# JKW_standalone.net
KiCad netlist of a schematic drawn in EAGLE
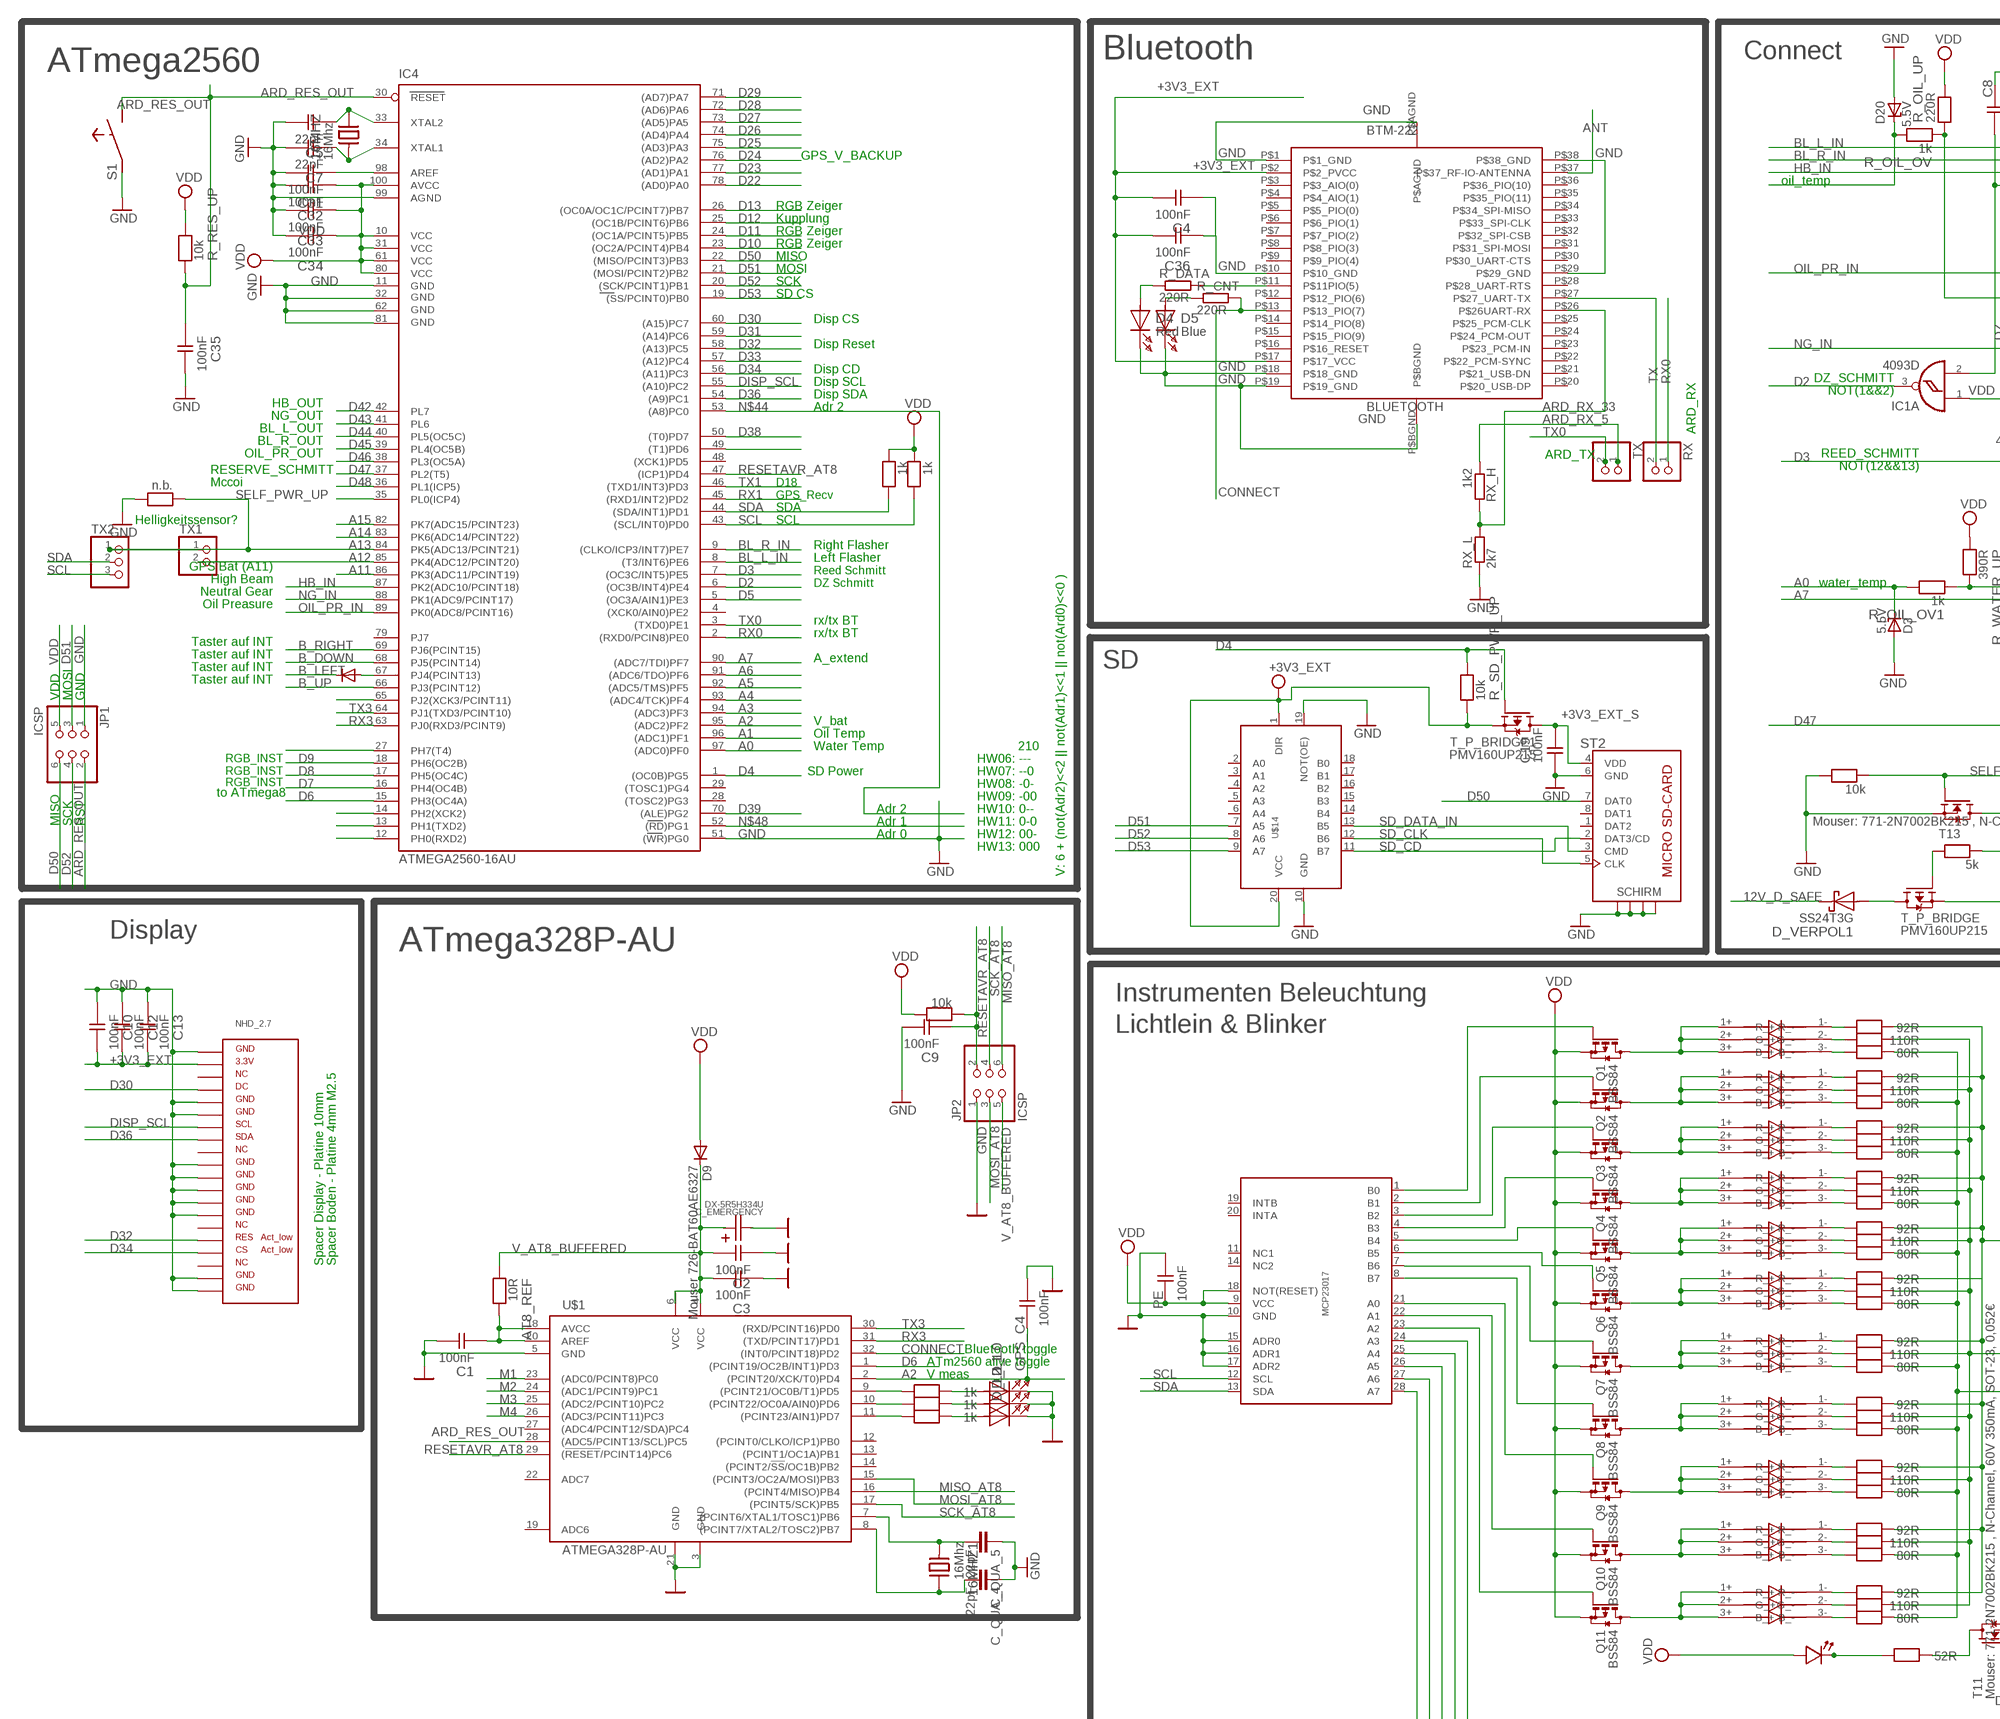
[diagram p0: schematic, sheet 1, part 1 of 3]
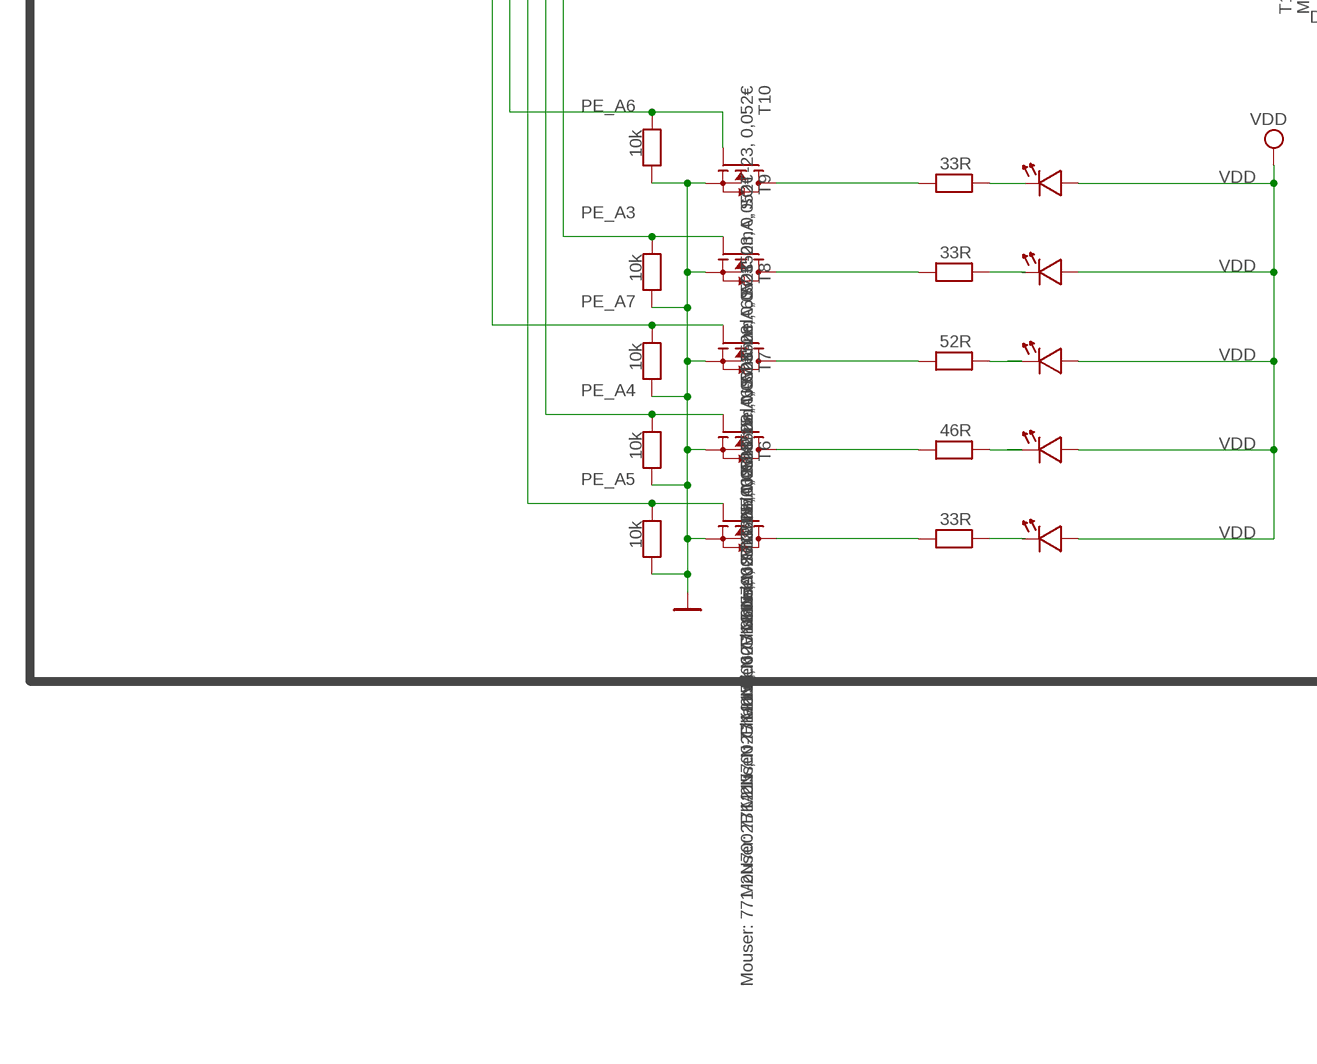
[diagram p1: schematic, sheet 1, part 2 of 3]
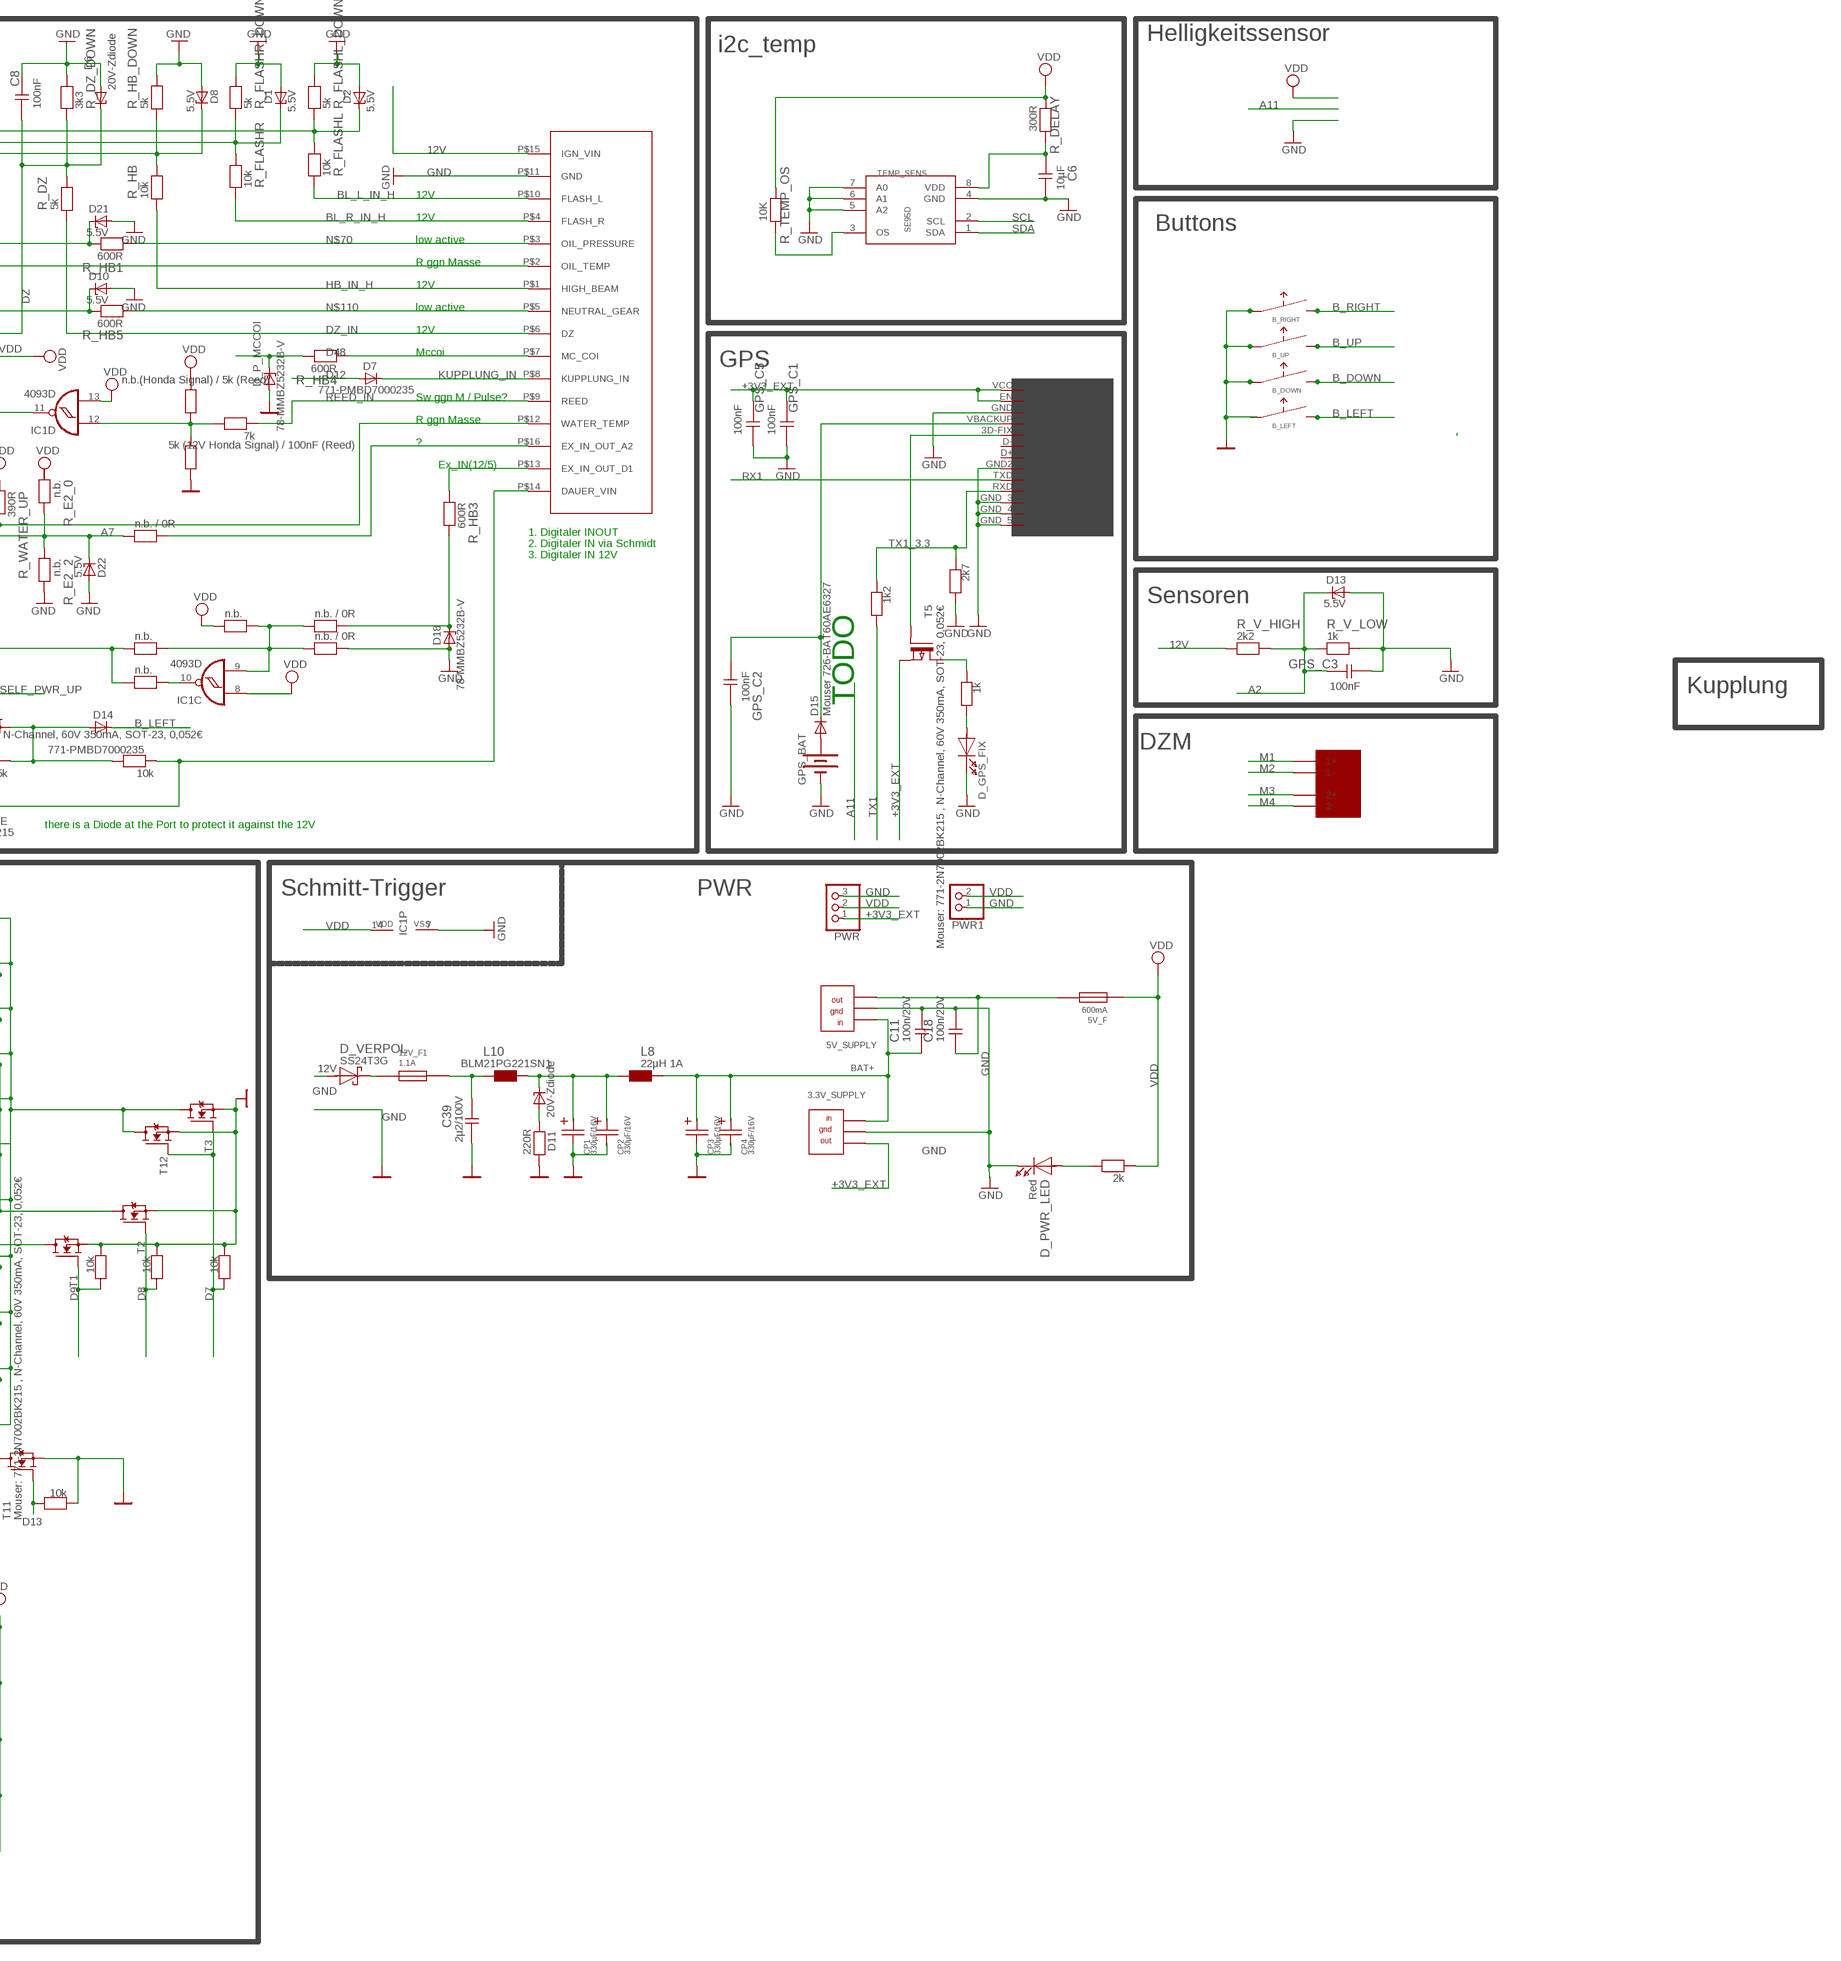
[diagram p2: schematic, sheet 1, part 3 of 3]

(export (version "E")
  (design (tool "Eeschema 10.0.6"))
  (components
    (comp (ref "3.3V_SUPPLY")
      (value "OKI78SR3.31.5WHC")
      (footprint "eagle-import:OKI-78SR")
      (libsource (lib "eagle-import") (part "OKI-78SR"))
    )
    (comp (ref "5V_F")
      (value "600mA")
      (footprint "eagle-import:POLY_FUSE")
      (libsource (lib "eagle-import") (part "POLY_FUSE"))
    )
    (comp (ref "5V_SUPPLY")
      (value "OKI78SR51.5W36HC")
      (footprint "eagle-import:OKI-78SR")
      (libsource (lib "eagle-import") (part "OKI-78SR"))
    )
    (comp (ref "12V_F1")
      (value "1.1A")
      (footprint "eagle-import:POLY_FUSE")
      (libsource (lib "eagle-import") (part "POLY_FUSE"))
    )
    (comp (ref "16MHZ")
      (value "16Mhz")
      (footprint "eagle-import:XT-HC49S-SMD")
      (libsource (lib "eagle-import") (part "XT-HC49-SMD"))
    )
    (comp (ref "16MHZ1")
      (value "16Mhz")
      (footprint "eagle-import:XT-HC49S-SMD")
      (libsource (lib "eagle-import") (part "XT-HC49-SMD"))
    )
    (comp (ref "AT8_REF")
      (value "10R")
      (footprint "eagle-import:0805")
      (libsource (lib "eagle-import") (part "R0805"))
    )
    (comp (ref "BLUETOOTH")
      (value "BTM-222")
      (footprint "eagle-import:BTM-222")
      (libsource (lib "eagle-import") (part "BTM-222"))
    )
    (comp (ref "B_DOWN")
      (value "SMD_TASTER_MIT_KAPPE")
      (footprint "eagle-import:SMD_DRUCKTASTER")
      (libsource (lib "eagle-import") (part "SMD_TASTER_MIT_KAPPE"))
    )
    (comp (ref "B_LEFT")
      (value "SMD_TASTER_MIT_KAPPE")
      (footprint "eagle-import:SMD_DRUCKTASTER")
      (libsource (lib "eagle-import") (part "SMD_TASTER_MIT_KAPPE"))
    )
    (comp (ref "B_RIGHT")
      (value "SMD_TASTER_MIT_KAPPE")
      (footprint "eagle-import:SMD_DRUCKTASTER")
      (libsource (lib "eagle-import") (part "SMD_TASTER_MIT_KAPPE"))
    )
    (comp (ref "B_UP")
      (value "SMD_TASTER_MIT_KAPPE")
      (footprint "eagle-import:SMD_DRUCKTASTER")
      (libsource (lib "eagle-import") (part "SMD_TASTER_MIT_KAPPE"))
    )
    (comp (ref "C1")
      (value "100nF")
      (footprint "eagle-import:0805")
      (libsource (lib "eagle-import") (part "C0805"))
    )
    (comp (ref "C2")
      (value "100nF")
      (footprint "eagle-import:0805")
      (libsource (lib "eagle-import") (part "C0805"))
    )
    (comp (ref "C3")
      (value "100nF")
      (footprint "eagle-import:0805")
      (libsource (lib "eagle-import") (part "C0805"))
    )
    (comp (ref "C4")
      (value "100nF")
      (footprint "eagle-import:0805")
      (libsource (lib "eagle-import") (part "C0805"))
    )
    (comp (ref "C5")
      (value "22pF")
      (footprint "eagle-import:0805")
      (libsource (lib "eagle-import") (part "C0805"))
    )
    (comp (ref "C6")
      (value "10µF")
      (footprint "eagle-import:0805")
      (libsource (lib "eagle-import") (part "C0805"))
    )
    (comp (ref "C7")
      (value "22pF")
      (footprint "eagle-import:0805")
      (libsource (lib "eagle-import") (part "C0805"))
    )
    (comp (ref "C8")
      (value "100nF")
      (footprint "eagle-import:0805")
      (libsource (lib "eagle-import") (part "C0805"))
    )
    (comp (ref "C9")
      (value "100nF")
      (footprint "eagle-import:0805")
      (libsource (lib "eagle-import") (part "C0805"))
    )
    (comp (ref "C10")
      (value "100nF")
      (footprint "eagle-import:0805")
      (libsource (lib "eagle-import") (part "C0805"))
    )
    (comp (ref "C11")
      (value "100n/20V")
      (footprint "eagle-import:0805")
      (libsource (lib "eagle-import") (part "C0805"))
    )
    (comp (ref "C12")
      (value "100nF")
      (footprint "eagle-import:0805")
      (libsource (lib "eagle-import") (part "C0805"))
    )
    (comp (ref "C13")
      (value "100nF")
      (footprint "eagle-import:0805")
      (libsource (lib "eagle-import") (part "C0805"))
    )
    (comp (ref "C18")
      (value "100n/20V")
      (footprint "eagle-import:0805")
      (libsource (lib "eagle-import") (part "C0805"))
    )
    (comp (ref "C19")
      (value "100nF")
      (footprint "eagle-import:0805")
      (libsource (lib "eagle-import") (part "C0805"))
    )
    (comp (ref "C31")
      (value "100nF")
      (footprint "eagle-import:0805")
      (libsource (lib "eagle-import") (part "C0805"))
    )
    (comp (ref "C32")
      (value "100nF")
      (footprint "eagle-import:0805")
      (libsource (lib "eagle-import") (part "C0805"))
    )
    (comp (ref "C33")
      (value "100nF")
      (footprint "eagle-import:0805")
      (libsource (lib "eagle-import") (part "C0805"))
    )
    (comp (ref "C34")
      (value "100nF")
      (footprint "eagle-import:0805")
      (libsource (lib "eagle-import") (part "C0805"))
    )
    (comp (ref "C35")
      (value "100nF")
      (footprint "eagle-import:0805")
      (libsource (lib "eagle-import") (part "C0805"))
    )
    (comp (ref "C36")
      (value "100nF")
      (footprint "eagle-import:0805")
      (libsource (lib "eagle-import") (part "C0805"))
    )
    (comp (ref "C39")
      (value "2µ2/100V")
      (footprint "eagle-import:0805")
      (libsource (lib "eagle-import") (part "C0805"))
    )
    (comp (ref "CP1")
      (value "330µF/16V")
      (footprint "eagle-import:SMD_SMT_6.6_6.6")
      (libsource (lib "eagle-import") (part "C_SMD_SMP"))
    )
    (comp (ref "CP2")
      (value "330µF/16V")
      (footprint "eagle-import:SMD_SMT_6.6_6.6")
      (libsource (lib "eagle-import") (part "C_SMD_SMP"))
    )
    (comp (ref "CP3")
      (value "330µF/16V")
      (footprint "eagle-import:SMD_SMT_6.6_6.6")
      (libsource (lib "eagle-import") (part "C_SMD_SMP"))
    )
    (comp (ref "CP4")
      (value "330µF/16V")
      (footprint "eagle-import:SMD_SMT_6.6_6.6")
      (libsource (lib "eagle-import") (part "C_SMD_SMP"))
    )
    (comp (ref "C_EMERGENCY")
      (value "DX-5R5H334U")
      (footprint "eagle-import:GOLDCAP")
      (libsource (lib "eagle-import") (part "DX-5R5H334U"))
    )
    (comp (ref "C_QUA_4")
      (value "22pF")
      (footprint "eagle-import:C0805")
      (libsource (lib "eagle-import") (part "C-EUC0805"))
    )
    (comp (ref "C_QUA_5")
      (value "22pF")
      (footprint "eagle-import:C0805")
      (libsource (lib "eagle-import") (part "C-EUC0805"))
    )
    (comp (ref "D1")
      (value "5.5V")
      (footprint "eagle-import:SOT23")
      (libsource (lib "eagle-import") (part "ZENER-DIODESOT23"))
    )
    (comp (ref "D2")
      (value "5.5V")
      (footprint "eagle-import:SOT23")
      (libsource (lib "eagle-import") (part "ZENER-DIODESOT23"))
    )
    (comp (ref "D3")
      (value "5.5V")
      (footprint "eagle-import:SOT23")
      (libsource (lib "eagle-import") (part "ZENER-DIODESOT23"))
    )
    (comp (ref "D4")
      (value "Red")
      (footprint "eagle-import:LED-0805")
      (libsource (lib "eagle-import") (part "LED0805"))
    )
    (comp (ref "D5")
      (value "Blue")
      (footprint "eagle-import:LED-0805")
      (libsource (lib "eagle-import") (part "LED0805"))
    )
    (comp (ref "D6")
      (value "20V-Zdiode")
      (footprint "eagle-import:SOT23")
      (libsource (lib "eagle-import") (part "ZENER-DIODESOT23"))
    )
    (comp (ref "D7")
      (value "771-PMBD7000235")
      (footprint "eagle-import:SOT23")
      (libsource (lib "eagle-import") (part "D-A1-C3"))
    )
    (comp (ref "D8")
      (value "5.5V")
      (footprint "eagle-import:SOT23")
      (libsource (lib "eagle-import") (part "ZENER-DIODESOT23"))
    )
    (comp (ref "D9")
      (value "Mouser 726-BAT60AE6327")
      (footprint "eagle-import:SOD323-W")
      (libsource (lib "eagle-import") (part "DIODE-SOD323-W"))
    )
    (comp (ref "D10")
      (value "5.5V")
      (footprint "eagle-import:SOT23")
      (libsource (lib "eagle-import") (part "ZENER-DIODESOT23"))
    )
    (comp (ref "D11")
      (value "20V-Zdiode")
      (footprint "eagle-import:SOT23")
      (libsource (lib "eagle-import") (part "ZENER-DIODESOT23"))
    )
    (comp (ref "D12")
      (value "771-PMBD7000235")
      (footprint "eagle-import:SOT23")
      (libsource (lib "eagle-import") (part "D-A1-C3"))
    )
    (comp (ref "D13")
      (value "5.5V")
      (footprint "eagle-import:SOT23")
      (libsource (lib "eagle-import") (part "ZENER-DIODESOT23"))
    )
    (comp (ref "D14")
      (value "771-PMBD7000235")
      (footprint "eagle-import:SOT23")
      (libsource (lib "eagle-import") (part "D-A1-C3"))
    )
    (comp (ref "D15")
      (value "Mouser 726-BAT60AE6327")
      (footprint "eagle-import:SOD323-W")
      (libsource (lib "eagle-import") (part "DIODE-SOD323-W"))
    )
    (comp (ref "D18")
      (value "78-MMBZ5232B-V")
      (footprint "eagle-import:SOT23")
      (libsource (lib "eagle-import") (part "ZENER-DIODESOT23"))
    )
    (comp (ref "D20")
      (value "5.5V")
      (footprint "eagle-import:SOT23")
      (libsource (lib "eagle-import") (part "ZENER-DIODESOT23"))
    )
    (comp (ref "D21")
      (value "5.5V")
      (footprint "eagle-import:SOT23")
      (libsource (lib "eagle-import") (part "ZENER-DIODESOT23"))
    )
    (comp (ref "D22")
      (value "5.5V")
      (footprint "eagle-import:SOT23")
      (libsource (lib "eagle-import") (part "ZENER-DIODESOT23"))
    )
    (comp (ref "D_GPS_FIX")
      (value "Red")
      (footprint "eagle-import:LED-0805")
      (libsource (lib "eagle-import") (part "LED0805"))
    )
    (comp (ref "D_GR_BLR")
      (value "PLCC4_LED")
      (footprint "eagle-import:PLCC-4")
      (libsource (lib "eagle-import") (part "PLCC4_LED"))
    )
    (comp (ref "D_GR_N")
      (value "PLCC4_LED")
      (footprint "eagle-import:PLCC-4")
      (libsource (lib "eagle-import") (part "PLCC4_LED"))
    )
    (comp (ref "D_L0")
      (value "LED0805")
      (footprint "eagle-import:LED-0805")
      (libsource (lib "eagle-import") (part "LED0805"))
    )
    (comp (ref "D_L1")
      (value "LED0805")
      (footprint "eagle-import:LED-0805")
      (libsource (lib "eagle-import") (part "LED0805"))
    )
    (comp (ref "D_L2")
      (value "LED0805")
      (footprint "eagle-import:LED-0805")
      (libsource (lib "eagle-import") (part "LED0805"))
    )
    (comp (ref "D_PWR_LED")
      (value "Red")
      (footprint "eagle-import:LED-0805")
      (libsource (lib "eagle-import") (part "LED0805"))
    )
    (comp (ref "D_P_MCCOI")
      (value "78-MMBZ5232B-V")
      (footprint "eagle-import:SOT23")
      (libsource (lib "eagle-import") (part "ZENER-DIODESOT23"))
    )
    (comp (ref "D_VERPOL")
      (value "SS24T3G")
      (footprint "eagle-import:SMB")
      (libsource (lib "eagle-import") (part "D-SSMB-A+K"))
    )
    (comp (ref "D_VERPOL1")
      (value "SS24T3G")
      (footprint "eagle-import:SMB")
      (libsource (lib "eagle-import") (part "D-SSMB-A+K"))
    )
    (comp (ref "GPS")
      (value "MT3329")
      (footprint "eagle-import:MT3329")
      (libsource (lib "eagle-import") (part "MT3329"))
    )
    (comp (ref "GPS_BAT")
      (value "F_908642")
      (footprint "eagle-import:BATTCON_12MM")
      (libsource (lib "eagle-import") (part "BATTERY12MM"))
    )
    (comp (ref "GPS_C1")
      (value "100nF")
      (footprint "eagle-import:0805")
      (libsource (lib "eagle-import") (part "C0805"))
    )
    (comp (ref "GPS_C2")
      (value "100nF")
      (footprint "eagle-import:0805")
      (libsource (lib "eagle-import") (part "C0805"))
    )
    (comp (ref "GPS_C3")
      (value "100nF")
      (footprint "eagle-import:0805")
      (libsource (lib "eagle-import") (part "C0805"))
    )
    (comp (ref "GPS_C4")
      (value "100nF")
      (footprint "eagle-import:0805")
      (libsource (lib "eagle-import") (part "C0805"))
    )
    (comp (ref "GPS_C5")
      (value "100nF")
      (footprint "eagle-import:0805")
      (libsource (lib "eagle-import") (part "C0805"))
    )
    (comp (ref "IC1")
      (value "4093D")
      (footprint "eagle-import:SO14")
      (libsource (lib "eagle-import") (part "4093D"))
    )
    (comp (ref "IC4")
      (value "ATMEGA2560-16AU")
      (footprint "eagle-import:TQFP100")
      (libsource (lib "eagle-import") (part "ATMEGAAU2560-16"))
    )
    (comp (ref "JP1")
      (value "ICSP")
      (footprint "eagle-import:2X03")
      (libsource (lib "eagle-import") (part "PINHD-2X3"))
    )
    (comp (ref "JP2")
      (value "ICSP")
      (footprint "eagle-import:2X03")
      (libsource (lib "eagle-import") (part "PINHD-2X3"))
    )
    (comp (ref "L8")
      (value "22µH 1A")
      (footprint "eagle-import:L-PD54")
      (libsource (lib "eagle-import") (part "LPD54"))
    )
    (comp (ref "L10")
      (value "BLM21PG221SN1")
      (footprint "eagle-import:0805+603")
      (libsource (lib "eagle-import") (part "L0808+0603"))
    )
    (comp (ref "NHD_2.7")
      (value "NHD_2.7_SOLO_RO")
      (footprint "eagle-import:NHD_2.7_SOLO_RO")
      (libsource (lib "eagle-import") (part "NHD_2.7_SOLO_RO"))
    )
    (comp (ref "PE")
      (value "100nF")
      (footprint "eagle-import:0805")
      (libsource (lib "eagle-import") (part "C0805"))
    )
    (comp (ref "PWR")
      (value "PINHD-1X3")
      (footprint "eagle-import:1X03")
      (libsource (lib "eagle-import") (part "PINHD-1X3"))
    )
    (comp (ref "PWR1")
      (value "PINHD-1X2")
      (footprint "eagle-import:1X02")
      (libsource (lib "eagle-import") (part "PINHD-1X2"))
    )
    (comp (ref "Q1")
      (value "BSS84")
      (footprint "eagle-import:SOT23")
      (libsource (lib "eagle-import") (part "BSS84"))
    )
    (comp (ref "Q2")
      (value "BSS84")
      (footprint "eagle-import:SOT23")
      (libsource (lib "eagle-import") (part "BSS84"))
    )
    (comp (ref "Q3")
      (value "BSS84")
      (footprint "eagle-import:SOT23")
      (libsource (lib "eagle-import") (part "BSS84"))
    )
    (comp (ref "Q4")
      (value "BSS84")
      (footprint "eagle-import:SOT23")
      (libsource (lib "eagle-import") (part "BSS84"))
    )
    (comp (ref "Q5")
      (value "BSS84")
      (footprint "eagle-import:SOT23")
      (libsource (lib "eagle-import") (part "BSS84"))
    )
    (comp (ref "Q6")
      (value "BSS84")
      (footprint "eagle-import:SOT23")
      (libsource (lib "eagle-import") (part "BSS84"))
    )
    (comp (ref "Q7")
      (value "BSS84")
      (footprint "eagle-import:SOT23")
      (libsource (lib "eagle-import") (part "BSS84"))
    )
    (comp (ref "Q8")
      (value "BSS84")
      (footprint "eagle-import:SOT23")
      (libsource (lib "eagle-import") (part "BSS84"))
    )
    (comp (ref "Q9")
      (value "BSS84")
      (footprint "eagle-import:SOT23")
      (libsource (lib "eagle-import") (part "BSS84"))
    )
    (comp (ref "Q10")
      (value "BSS84")
      (footprint "eagle-import:SOT23")
      (libsource (lib "eagle-import") (part "BSS84"))
    )
    (comp (ref "Q11")
      (value "BSS84")
      (footprint "eagle-import:SOT23")
      (libsource (lib "eagle-import") (part "BSS84"))
    )
    (comp (ref "RGB_1")
      (value "RGB_LED")
      (footprint "eagle-import:PLCC-6")
      (libsource (lib "eagle-import") (part "RGB_LED"))
    )
    (comp (ref "RGB_2")
      (value "RGB_LED")
      (footprint "eagle-import:PLCC-6")
      (libsource (lib "eagle-import") (part "RGB_LED"))
    )
    (comp (ref "RGB_3")
      (value "RGB_LED")
      (footprint "eagle-import:PLCC-6")
      (libsource (lib "eagle-import") (part "RGB_LED"))
    )
    (comp (ref "RGB_4")
      (value "RGB_LED")
      (footprint "eagle-import:PLCC-6")
      (libsource (lib "eagle-import") (part "RGB_LED"))
    )
    (comp (ref "RGB_5")
      (value "RGB_LED")
      (footprint "eagle-import:PLCC-6")
      (libsource (lib "eagle-import") (part "RGB_LED"))
    )
    (comp (ref "RGB_6")
      (value "RGB_LED")
      (footprint "eagle-import:PLCC-6")
      (libsource (lib "eagle-import") (part "RGB_LED"))
    )
    (comp (ref "RGB_7")
      (value "RGB_LED")
      (footprint "eagle-import:PLCC-6")
      (libsource (lib "eagle-import") (part "RGB_LED"))
    )
    (comp (ref "RGB_8")
      (value "RGB_LED")
      (footprint "eagle-import:PLCC-6")
      (libsource (lib "eagle-import") (part "RGB_LED"))
    )
    (comp (ref "RGB_9")
      (value "RGB_LED")
      (footprint "eagle-import:PLCC-6")
      (libsource (lib "eagle-import") (part "RGB_LED"))
    )
    (comp (ref "RGB_10")
      (value "RGB_LED")
      (footprint "eagle-import:PLCC-6")
      (libsource (lib "eagle-import") (part "RGB_LED"))
    )
    (comp (ref "RGB_11")
      (value "RGB_LED")
      (footprint "eagle-import:PLCC-6")
      (libsource (lib "eagle-import") (part "RGB_LED"))
    )
    (comp (ref "RX")
      (value "PINHD-1X2")
      (footprint "eagle-import:1X02")
      (libsource (lib "eagle-import") (part "PINHD-1X2"))
    )
    (comp (ref "RX_H")
      (value "1k2")
      (footprint "eagle-import:M0805")
      (libsource (lib "eagle-import") (part "resistor_R-EU_M0805"))
    )
    (comp (ref "RX_L")
      (value "2k7")
      (footprint "eagle-import:M0805")
      (libsource (lib "eagle-import") (part "resistor_R-EU_M0805"))
    )
    (comp (ref "R_BL_L")
      (value "33R")
      (footprint "eagle-import:0805")
      (libsource (lib "eagle-import") (part "R0805"))
    )
    (comp (ref "R_BL_L1")
      (value "n.b.")
      (footprint "eagle-import:0805")
      (libsource (lib "eagle-import") (part "R0805"))
    )
    (comp (ref "R_BL_R")
      (value "33R")
      (footprint "eagle-import:0805")
      (libsource (lib "eagle-import") (part "R0805"))
    )
    (comp (ref "R_B_LED_1")
      (value "80R")
      (footprint "eagle-import:0805")
      (libsource (lib "eagle-import") (part "R0805"))
    )
    (comp (ref "R_B_LED_2")
      (value "80R")
      (footprint "eagle-import:0805")
      (libsource (lib "eagle-import") (part "R0805"))
    )
    (comp (ref "R_B_LED_3")
      (value "80R")
      (footprint "eagle-import:0805")
      (libsource (lib "eagle-import") (part "R0805"))
    )
    (comp (ref "R_B_LED_4")
      (value "80R")
      (footprint "eagle-import:0805")
      (libsource (lib "eagle-import") (part "R0805"))
    )
    (comp (ref "R_B_LED_5")
      (value "80R")
      (footprint "eagle-import:0805")
      (libsource (lib "eagle-import") (part "R0805"))
    )
    (comp (ref "R_B_LED_6")
      (value "80R")
      (footprint "eagle-import:0805")
      (libsource (lib "eagle-import") (part "R0805"))
    )
    (comp (ref "R_B_LED_7")
      (value "80R")
      (footprint "eagle-import:0805")
      (libsource (lib "eagle-import") (part "R0805"))
    )
    (comp (ref "R_B_LED_8")
      (value "80R")
      (footprint "eagle-import:0805")
      (libsource (lib "eagle-import") (part "R0805"))
    )
    (comp (ref "R_B_LED_9")
      (value "80R")
      (footprint "eagle-import:0805")
      (libsource (lib "eagle-import") (part "R0805"))
    )
    (comp (ref "R_B_LED_10")
      (value "80R")
      (footprint "eagle-import:0805")
      (libsource (lib "eagle-import") (part "R0805"))
    )
    (comp (ref "R_B_LED_11")
      (value "80R")
      (footprint "eagle-import:0805")
      (libsource (lib "eagle-import") (part "R0805"))
    )
    (comp (ref "R_B_LED_12")
      (value "10k")
      (footprint "eagle-import:0805")
      (libsource (lib "eagle-import") (part "R0805"))
    )
    (comp (ref "R_B_LED_13")
      (value "10k")
      (footprint "eagle-import:0805")
      (libsource (lib "eagle-import") (part "R0805"))
    )
    (comp (ref "R_B_LED_14")
      (value "10k")
      (footprint "eagle-import:0805")
      (libsource (lib "eagle-import") (part "R0805"))
    )
    (comp (ref "R_B_LED_15")
      (value "10k")
      (footprint "eagle-import:0805")
      (libsource (lib "eagle-import") (part "R0805"))
    )
    (comp (ref "R_B_LED_16")
      (value "10k")
      (footprint "eagle-import:0805")
      (libsource (lib "eagle-import") (part "R0805"))
    )
    (comp (ref "R_B_LED_17")
      (value "10k")
      (footprint "eagle-import:0805")
      (libsource (lib "eagle-import") (part "R0805"))
    )
    (comp (ref "R_B_LED_18")
      (value "10k")
      (footprint "eagle-import:0805")
      (libsource (lib "eagle-import") (part "R0805"))
    )
    (comp (ref "R_B_LED_19")
      (value "10k")
      (footprint "eagle-import:0805")
      (libsource (lib "eagle-import") (part "R0805"))
    )
    (comp (ref "R_B_LED_20")
      (value "10k")
      (footprint "eagle-import:0805")
      (libsource (lib "eagle-import") (part "R0805"))
    )
    (comp (ref "R_CNT")
      (value "220R")
      (footprint "eagle-import:M0805")
      (libsource (lib "eagle-import") (part "R-EU_M0805"))
    )
    (comp (ref "R_DATA")
      (value "220R")
      (footprint "eagle-import:M0805")
      (libsource (lib "eagle-import") (part "R-EU_M0805"))
    )
    (comp (ref "R_DEAKT_DAUER_P")
      (value "10k")
      (footprint "eagle-import:0805")
      (libsource (lib "eagle-import") (part "R0805"))
    )
    (comp (ref "R_DEAKT_DAUER_P1")
      (value "10k")
      (footprint "eagle-import:0805")
      (libsource (lib "eagle-import") (part "R0805"))
    )
    (comp (ref "R_DEAKT_DAUER_P2")
      (value "5k")
      (footprint "eagle-import:0805")
      (libsource (lib "eagle-import") (part "R0805"))
    )
    (comp (ref "R_DELAY")
      (value "300R")
      (footprint "eagle-import:0805")
      (libsource (lib "eagle-import") (part "R0805"))
    )
    (comp (ref "R_DZ")
      (value "5k")
      (footprint "eagle-import:0805")
      (libsource (lib "eagle-import") (part "R0805"))
    )
    (comp (ref "R_DZ_DOWN")
      (value "3k3")
      (footprint "eagle-import:0805")
      (libsource (lib "eagle-import") (part "R0805"))
    )
    (comp (ref "R_E1_0")
      (value "n.b.")
      (footprint "eagle-import:0805")
      (libsource (lib "eagle-import") (part "R0805"))
    )
    (comp (ref "R_E1_1")
      (value "n.b. / 0R")
      (footprint "eagle-import:0805")
      (libsource (lib "eagle-import") (part "R0805"))
    )
    (comp (ref "R_E1_2")
      (value "n.b.")
      (footprint "eagle-import:0805")
      (libsource (lib "eagle-import") (part "R0805"))
    )
    (comp (ref "R_E1_3")
      (value "n.b. / 0R")
      (footprint "eagle-import:0805")
      (libsource (lib "eagle-import") (part "R0805"))
    )
    (comp (ref "R_E1_4")
      (value "n.b.")
      (footprint "eagle-import:0805")
      (libsource (lib "eagle-import") (part "R0805"))
    )
    (comp (ref "R_E2_0")
      (value "n.b.")
      (footprint "eagle-import:0805")
      (libsource (lib "eagle-import") (part "R0805"))
    )
    (comp (ref "R_E2_1")
      (value "n.b. / 0R")
      (footprint "eagle-import:0805")
      (libsource (lib "eagle-import") (part "R0805"))
    )
    (comp (ref "R_E2_2")
      (value "n.b.")
      (footprint "eagle-import:0805")
      (libsource (lib "eagle-import") (part "R0805"))
    )
    (comp (ref "R_FLASHL")
      (value "10k")
      (footprint "eagle-import:0805")
      (libsource (lib "eagle-import") (part "R0805"))
    )
    (comp (ref "R_FLASHL_DOWN")
      (value "5k")
      (footprint "eagle-import:0805")
      (libsource (lib "eagle-import") (part "R0805"))
    )
    (comp (ref "R_FLASHR")
      (value "10k")
      (footprint "eagle-import:0805")
      (libsource (lib "eagle-import") (part "R0805"))
    )
    (comp (ref "R_FLASHR_DOWN")
      (value "5k")
      (footprint "eagle-import:0805")
      (libsource (lib "eagle-import") (part "R0805"))
    )
    (comp (ref "R_GPS_LED")
      (value "1k")
      (footprint "eagle-import:0805")
      (libsource (lib "eagle-import") (part "R0805"))
    )
    (comp (ref "R_GR_BL_L")
      (value "PLCC4_LED")
      (footprint "eagle-import:PLCC-4")
      (libsource (lib "eagle-import") (part "PLCC4_LED"))
    )
    (comp (ref "R_G_LED_1")
      (value "110R")
      (footprint "eagle-import:0805")
      (libsource (lib "eagle-import") (part "R0805"))
    )
    (comp (ref "R_G_LED_2")
      (value "110R")
      (footprint "eagle-import:0805")
      (libsource (lib "eagle-import") (part "R0805"))
    )
    (comp (ref "R_G_LED_3")
      (value "110R")
      (footprint "eagle-import:0805")
      (libsource (lib "eagle-import") (part "R0805"))
    )
    (comp (ref "R_G_LED_4")
      (value "110R")
      (footprint "eagle-import:0805")
      (libsource (lib "eagle-import") (part "R0805"))
    )
    (comp (ref "R_G_LED_5")
      (value "110R")
      (footprint "eagle-import:0805")
      (libsource (lib "eagle-import") (part "R0805"))
    )
    (comp (ref "R_G_LED_6")
      (value "110R")
      (footprint "eagle-import:0805")
      (libsource (lib "eagle-import") (part "R0805"))
    )
    (comp (ref "R_G_LED_7")
      (value "110R")
      (footprint "eagle-import:0805")
      (libsource (lib "eagle-import") (part "R0805"))
    )
    (comp (ref "R_G_LED_8")
      (value "110R")
      (footprint "eagle-import:0805")
      (libsource (lib "eagle-import") (part "R0805"))
    )
    (comp (ref "R_G_LED_9")
      (value "110R")
      (footprint "eagle-import:0805")
      (libsource (lib "eagle-import") (part "R0805"))
    )
    (comp (ref "R_G_LED_10")
      (value "110R")
      (footprint "eagle-import:0805")
      (libsource (lib "eagle-import") (part "R0805"))
    )
    (comp (ref "R_G_LED_11")
      (value "110R")
      (footprint "eagle-import:0805")
      (libsource (lib "eagle-import") (part "R0805"))
    )
    (comp (ref "R_HB")
      (value "10k")
      (footprint "eagle-import:0805")
      (libsource (lib "eagle-import") (part "R0805"))
    )
    (comp (ref "R_HB1")
      (value "600R")
      (footprint "eagle-import:0805")
      (libsource (lib "eagle-import") (part "R0805"))
    )
    (comp (ref "R_HB3")
      (value "600R")
      (footprint "eagle-import:0805")
      (libsource (lib "eagle-import") (part "R0805"))
    )
    (comp (ref "R_HB4")
      (value "600R")
      (footprint "eagle-import:0805")
      (libsource (lib "eagle-import") (part "R0805"))
    )
    (comp (ref "R_HB5")
      (value "600R")
      (footprint "eagle-import:0805")
      (libsource (lib "eagle-import") (part "R0805"))
    )
    (comp (ref "R_HB_DOWN")
      (value "5k")
      (footprint "eagle-import:0805")
      (libsource (lib "eagle-import") (part "R0805"))
    )
    (comp (ref "R_HIGHB")
      (value "46R")
      (footprint "eagle-import:0805")
      (libsource (lib "eagle-import") (part "R0805"))
    )
    (comp (ref "R_L0")
      (value "1k")
      (footprint "eagle-import:0805")
      (libsource (lib "eagle-import") (part "R0805"))
    )
    (comp (ref "R_L1")
      (value "1k")
      (footprint "eagle-import:0805")
      (libsource (lib "eagle-import") (part "R0805"))
    )
    (comp (ref "R_L2")
      (value "1k")
      (footprint "eagle-import:0805")
      (libsource (lib "eagle-import") (part "R0805"))
    )
    (comp (ref "R_L3")
      (value "10k")
      (footprint "eagle-import:0805")
      (libsource (lib "eagle-import") (part "R0805"))
    )
    (comp (ref "R_LED_5V")
      (value "2k")
      (footprint "eagle-import:0805")
      (libsource (lib "eagle-import") (part "R0805"))
    )
    (comp (ref "R_N")
      (value "33R")
      (footprint "eagle-import:0805")
      (libsource (lib "eagle-import") (part "R0805"))
    )
    (comp (ref "R_OIL")
      (value "52R")
      (footprint "eagle-import:0805")
      (libsource (lib "eagle-import") (part "R0805"))
    )
    (comp (ref "R_OIL_OV")
      (value "1k")
      (footprint "eagle-import:0805")
      (libsource (lib "eagle-import") (part "R0805"))
    )
    (comp (ref "R_OIL_OV1")
      (value "1k")
      (footprint "eagle-import:0805")
      (libsource (lib "eagle-import") (part "R0805"))
    )
    (comp (ref "R_OIL_UP")
      (value "220R")
      (footprint "eagle-import:0805")
      (libsource (lib "eagle-import") (part "R0805"))
    )
    (comp (ref "R_REED")
      (value "7k")
      (footprint "eagle-import:0805")
      (libsource (lib "eagle-import") (part "R0805"))
    )
    (comp (ref "R_REED_DOWN")
      (value "5k (12V Honda Signal) / 100nF (Reed)")
      (footprint "eagle-import:0805")
      (libsource (lib "eagle-import") (part "R0805"))
    )
    (comp (ref "R_REED_UP")
      (value "n.b.(Honda Signal) / 5k (Reed)")
      (footprint "eagle-import:0805")
      (libsource (lib "eagle-import") (part "R0805"))
    )
    (comp (ref "R_RES_UP")
      (value "10k")
      (footprint "eagle-import:0805")
      (libsource (lib "eagle-import") (part "R0805"))
    )
    (comp (ref "R_R_LED_0")
      (value "52R")
      (footprint "eagle-import:0805")
      (libsource (lib "eagle-import") (part "R0805"))
    )
    (comp (ref "R_R_LED_1")
      (value "92R")
      (footprint "eagle-import:0805")
      (libsource (lib "eagle-import") (part "R0805"))
    )
    (comp (ref "R_R_LED_2")
      (value "92R")
      (footprint "eagle-import:0805")
      (libsource (lib "eagle-import") (part "R0805"))
    )
    (comp (ref "R_R_LED_3")
      (value "92R")
      (footprint "eagle-import:0805")
      (libsource (lib "eagle-import") (part "R0805"))
    )
    (comp (ref "R_R_LED_4")
      (value "92R")
      (footprint "eagle-import:0805")
      (libsource (lib "eagle-import") (part "R0805"))
    )
    (comp (ref "R_R_LED_5")
      (value "92R")
      (footprint "eagle-import:0805")
      (libsource (lib "eagle-import") (part "R0805"))
    )
    (comp (ref "R_R_LED_6")
      (value "92R")
      (footprint "eagle-import:0805")
      (libsource (lib "eagle-import") (part "R0805"))
    )
    (comp (ref "R_R_LED_7")
      (value "92R")
      (footprint "eagle-import:0805")
      (libsource (lib "eagle-import") (part "R0805"))
    )
    (comp (ref "R_R_LED_8")
      (value "92R")
      (footprint "eagle-import:0805")
      (libsource (lib "eagle-import") (part "R0805"))
    )
    (comp (ref "R_R_LED_9")
      (value "92R")
      (footprint "eagle-import:0805")
      (libsource (lib "eagle-import") (part "R0805"))
    )
    (comp (ref "R_R_LED_10")
      (value "92R")
      (footprint "eagle-import:0805")
      (libsource (lib "eagle-import") (part "R0805"))
    )
    (comp (ref "R_R_LED_11")
      (value "92R")
      (footprint "eagle-import:0805")
      (libsource (lib "eagle-import") (part "R0805"))
    )
    (comp (ref "R_R_LED_12")
      (value "220R")
      (footprint "eagle-import:0805")
      (libsource (lib "eagle-import") (part "R0805"))
    )
    (comp (ref "R_SCL_UP")
      (value "1k")
      (footprint "eagle-import:0805")
      (libsource (lib "eagle-import") (part "R0805"))
    )
    (comp (ref "R_SDA_UP")
      (value "1k")
      (footprint "eagle-import:0805")
      (libsource (lib "eagle-import") (part "R0805"))
    )
    (comp (ref "R_SD_PWR_UP")
      (value "10k")
      (footprint "eagle-import:0805")
      (libsource (lib "eagle-import") (part "R0805"))
    )
    (comp (ref "R_TEMP_OS")
      (value "10K")
      (footprint "eagle-import:0805")
      (libsource (lib "eagle-import") (part "R0805"))
    )
    (comp (ref "R_TX_DOWN")
      (value "2k7")
      (footprint "eagle-import:0805")
      (libsource (lib "eagle-import") (part "R0805"))
    )
    (comp (ref "R_TX_UP")
      (value "1k2")
      (footprint "eagle-import:0805")
      (libsource (lib "eagle-import") (part "R0805"))
    )
    (comp (ref "R_V_HIGH")
      (value "2k2")
      (footprint "eagle-import:0805")
      (libsource (lib "eagle-import") (part "R0805"))
    )
    (comp (ref "R_V_LOW")
      (value "1k")
      (footprint "eagle-import:0805")
      (libsource (lib "eagle-import") (part "R0805"))
    )
    (comp (ref "R_WATER_UP")
      (value "390R")
      (footprint "eagle-import:0805")
      (libsource (lib "eagle-import") (part "R0805"))
    )
    (comp (ref "S1")
      (value "SW-TASTERECO-DIAGONAL")
      (footprint "eagle-import:SW-ECO")
      (libsource (lib "eagle-import") (part "SW-TASTERECO-DIAGONAL"))
    )
    (comp (ref "SPEEDOSTECKER")
      (value "SPEEDOSTECKER")
      (footprint "eagle-import:SPEEDOSTECKER")
      (libsource (lib "eagle-import") (part "SPEEDOSTECKER"))
    )
    (comp (ref "ST2")
      (value "SD_MICRO")
      (footprint "eagle-import:SD_MICRO")
      (libsource (lib "eagle-import") (part "SD_MICRO"))
    )
    (comp (ref "STEPPER")
      (value "STEPPER")
      (footprint "eagle-import:STEPPER")
      (libsource (lib "eagle-import") (part "STEPPER"))
    )
    (comp (ref "T1")
      (value "Mouser: 771-2N7002BK215 , N-Channel, 60V 350mA, SOT-23, 0,052€")
      (footprint "eagle-import:SOT23")
      (libsource (lib "eagle-import") (part "2N7002"))
    )
    (comp (ref "T2")
      (value "Mouser: 771-2N7002BK215 , N-Channel, 60V 350mA, SOT-23, 0,052€")
      (footprint "eagle-import:SOT23")
      (libsource (lib "eagle-import") (part "2N7002"))
    )
    (comp (ref "T3")
      (value "Mouser: 771-2N7002BK215 , N-Channel, 60V 350mA, SOT-23, 0,052€")
      (footprint "eagle-import:SOT23")
      (libsource (lib "eagle-import") (part "2N7002"))
    )
    (comp (ref "T5")
      (value "Mouser: 771-2N7002BK215 , N-Channel, 60V 350mA, SOT-23, 0,052€")
      (footprint "eagle-import:SOT-23")
      (libsource (lib "eagle-import") (part "T-P-FETBSS139"))
    )
    (comp (ref "T6")
      (value "Mouser: 771-2N7002BK215 , N-Channel, 60V 350mA, SOT-23, 0,052€")
      (footprint "eagle-import:SOT23")
      (libsource (lib "eagle-import") (part "2N7002"))
    )
    (comp (ref "T7")
      (value "Mouser: 771-2N7002BK215 , N-Channel, 60V 350mA, SOT-23, 0,052€")
      (footprint "eagle-import:SOT23")
      (libsource (lib "eagle-import") (part "2N7002"))
    )
    (comp (ref "T8")
      (value "Mouser: 771-2N7002BK215 , N-Channel, 60V 350mA, SOT-23, 0,052€")
      (footprint "eagle-import:SOT23")
      (libsource (lib "eagle-import") (part "2N7002"))
    )
    (comp (ref "T9")
      (value "Mouser: 771-2N7002BK215 , N-Channel, 60V 350mA, SOT-23, 0,052€")
      (footprint "eagle-import:SOT23")
      (libsource (lib "eagle-import") (part "2N7002"))
    )
    (comp (ref "T10")
      (value "Mouser: 771-2N7002BK215 , N-Channel, 60V 350mA, SOT-23, 0,052€")
      (footprint "eagle-import:SOT23")
      (libsource (lib "eagle-import") (part "2N7002"))
    )
    (comp (ref "T11")
      (value "Mouser: 771-2N7002BK215 , N-Channel, 60V 350mA, SOT-23, 0,052€")
      (footprint "eagle-import:SOT23")
      (libsource (lib "eagle-import") (part "2N7002"))
    )
    (comp (ref "T12")
      (value "Mouser: 771-2N7002BK215 , N-Channel, 60V 350mA, SOT-23, 0,052€")
      (footprint "eagle-import:SOT23")
      (libsource (lib "eagle-import") (part "2N7002"))
    )
    (comp (ref "T13")
      (value "Mouser: 771-2N7002BK215 , N-Channel, 60V 350mA, SOT-23, 0,052€")
      (footprint "eagle-import:SOT23")
      (libsource (lib "eagle-import") (part "2N7002"))
    )
    (comp (ref "TEMP_SENS")
      (value "SE95D")
      (footprint "eagle-import:SOIC8")
      (libsource (lib "eagle-import") (part "SE95D"))
    )
    (comp (ref "TX")
      (value "PINHD-1X2")
      (footprint "eagle-import:1X02")
      (libsource (lib "eagle-import") (part "PINHD-1X2"))
    )
    (comp (ref "TX1")
      (value "PINHD-1X2")
      (footprint "eagle-import:1X02")
      (libsource (lib "eagle-import") (part "PINHD-1X2"))
    )
    (comp (ref "TX2")
      (value "PINHD-1X3")
      (footprint "eagle-import:1X03")
      (libsource (lib "eagle-import") (part "PINHD-1X3"))
    )
    (comp (ref "T_P_BRIDGE")
      (value "PMV160UP215")
      (footprint "eagle-import:SOT23")
      (libsource (lib "eagle-import") (part "PMV160UP215"))
    )
    (comp (ref "T_P_BRIDGE1")
      (value "PMV160UP215")
      (footprint "eagle-import:SOT23")
      (libsource (lib "eagle-import") (part "PMV160UP215"))
    )
    (comp (ref "U$1")
      (value "ATMEGA328P-AU")
      (footprint "eagle-import:TQFP8")
      (libsource (lib "eagle-import") (part "ATMEGA328P-AU"))
    )
    (comp (ref "U$3")
      (value "CLM4B-BKW-CTBVA363")
      (footprint "eagle-import:PLCC-4")
      (libsource (lib "eagle-import") (part "CLM4B-BKW-CTBVA363"))
    )
    (comp (ref "U$11")
      (value "CLM4B-RKW-CWAXBAA3")
      (footprint "eagle-import:PLCC-4")
      (libsource (lib "eagle-import") (part "CLM4B-RKW-CWAXBAA3"))
    )
    (comp (ref "U$14")
      (value "74LVC_LVCH245A")
      (footprint "eagle-import:TSSOP20")
      (libsource (lib "eagle-import") (part "74LVC_LVCH245A"))
    )
    (comp (ref "U$19")
      (value "MCP23017")
      (footprint "eagle-import:SOIC28")
      (libsource (lib "eagle-import") (part "MCP23017"))
    )
    (comp (ref "U$22")
      (value "CLM4B-RKW-CWAXBAA3")
      (footprint "eagle-import:PLCC-4")
      (libsource (lib "eagle-import") (part "CLM4B-RKW-CWAXBAA3"))
    )
  )
  (nets
    (net (code "1") (name "+3V3_EXT") (class "Default")
      (node (ref "3.3V_SUPPLY") (pin "OUT") (pinfunction "OUT_OUT") (pintype "bidirectional"))
      (node (ref "BLUETOOTH") (pin "P$17") (pinfunction "P$17_VCC_P$17") (pintype "power_in"))
      (node (ref "BLUETOOTH") (pin "P$2") (pinfunction "P$2_PVCC_P$2") (pintype "power_in"))
      (node (ref "C10") (pin "2") (pinfunction "2_2") (pintype "passive"))
      (node (ref "C12") (pin "2") (pinfunction "2_2") (pintype "passive"))
      (node (ref "C13") (pin "2") (pinfunction "2_2") (pintype "passive"))
      (node (ref "C36") (pin "2") (pinfunction "2_2") (pintype "passive"))
      (node (ref "C4") (pin "2") (pinfunction "2_2") (pintype "passive"))
      (node (ref "GPS") (pin "EN") (pinfunction "EN_EN") (pintype "bidirectional"))
      (node (ref "GPS") (pin "VCC") (pinfunction "VCC_VCC") (pintype "bidirectional"))
      (node (ref "GPS_C1") (pin "2") (pinfunction "2_2") (pintype "passive"))
      (node (ref "GPS_C5") (pin "2") (pinfunction "2_2") (pintype "passive"))
      (node (ref "NHD_2.7") (pin "VDD0") (pinfunction "VDD_VDD0") (pintype "power_in"))
      (node (ref "PWR") (pin "1") (pinfunction "1_1") (pintype "passive"))
      (node (ref "R_SD_PWR_UP") (pin "1") (pinfunction "1_1") (pintype "passive"))
      (node (ref "T5") (pin "2") (pinfunction "S_2") (pintype "bidirectional"))
      (node (ref "T_P_BRIDGE1") (pin "2") (pinfunction "S_2") (pintype "passive"))
      (node (ref "U$14") (pin "1") (pinfunction "DIR_1") (pintype "bidirectional"))
      (node (ref "U$14") (pin "20") (pinfunction "VCC_20") (pintype "bidirectional"))
    )
    (net (code "2") (name "/+3V3_EXT_S") (class "Default")
      (node (ref "C19") (pin "2") (pinfunction "2_2") (pintype "passive"))
      (node (ref "ST2") (pin "4") (pinfunction "VDD_4") (pintype "bidirectional"))
      (node (ref "T_P_BRIDGE1") (pin "3") (pinfunction "D_3") (pintype "passive"))
    )
    (net (code "3") (name "/12V") (class "Default")
      (node (ref "D_VERPOL") (pin "A") (pinfunction "A_A") (pintype "passive"))
      (node (ref "R_V_HIGH") (pin "1") (pinfunction "1_1") (pintype "passive"))
      (node (ref "SPEEDOSTECKER") (pin "P$15") (pinfunction "IGN_VIN_P$15") (pintype "power_in"))
    )
    (net (code "4") (name "/12V_D_SAFE") (class "Default")
      (node (ref "12V_F1") (pin "P$1") (pinfunction "P$1_P$1") (pintype "bidirectional"))
      (node (ref "D_VERPOL") (pin "K") (pinfunction "K_K") (pintype "passive"))
      (node (ref "D_VERPOL1") (pin "K") (pinfunction "K_K") (pintype "passive"))
    )
    (net (code "5") (name "/A0") (class "Default")
      (node (ref "D3") (pin "3") (pinfunction "C_3") (pintype "passive"))
      (node (ref "IC4") (pin "97") (pinfunction "(ADC0)PF0_97") (pintype "bidirectional"))
      (node (ref "R_OIL_OV1") (pin "2") (pinfunction "2_2") (pintype "passive"))
    )
    (net (code "6") (name "/A1") (class "Default")
      (node (ref "D20") (pin "3") (pinfunction "C_3") (pintype "passive"))
      (node (ref "IC4") (pin "96") (pinfunction "(ADC1)PF1_96") (pintype "bidirectional"))
      (node (ref "R_OIL_OV") (pin "2") (pinfunction "2_2") (pintype "passive"))
    )
    (net (code "7") (name "/A2") (class "Default")
      (node (ref "D13") (pin "3") (pinfunction "C_3") (pintype "passive"))
      (node (ref "GPS_C3") (pin "2") (pinfunction "2_2") (pintype "passive"))
      (node (ref "GPS_C4") (pin "2") (pinfunction "2_2") (pintype "passive"))
      (node (ref "IC4") (pin "95") (pinfunction "(ADC2)PF2_95") (pintype "bidirectional"))
      (node (ref "R_V_HIGH") (pin "2") (pinfunction "2_2") (pintype "passive"))
      (node (ref "R_V_LOW") (pin "1") (pinfunction "1_1") (pintype "passive"))
      (node (ref "U$1") (pin "2") (pinfunction "(PCINT20/XCK/T0)PD4_2") (pintype "bidirectional"))
    )
    (net (code "8") (name "/A3") (class "Default")
      (node (ref "IC4") (pin "94") (pinfunction "(ADC3)PF3_94") (pintype "bidirectional"))
    )
    (net (code "9") (name "/A4") (class "Default")
      (node (ref "IC4") (pin "93") (pinfunction "(ADC4/TCK)PF4_93") (pintype "bidirectional"))
    )
    (net (code "10") (name "/A5") (class "Default")
      (node (ref "IC4") (pin "92") (pinfunction "(ADC5/TMS)PF5_92") (pintype "bidirectional"))
    )
    (net (code "11") (name "/A6") (class "Default")
      (node (ref "IC4") (pin "91") (pinfunction "(ADC6/TDO)PF6_91") (pintype "bidirectional"))
    )
    (net (code "12") (name "/A7") (class "Default")
      (node (ref "D22") (pin "3") (pinfunction "C_3") (pintype "passive"))
      (node (ref "IC4") (pin "90") (pinfunction "(ADC7/TDI)PF7_90") (pintype "bidirectional"))
      (node (ref "R_E2_0") (pin "2") (pinfunction "2_2") (pintype "passive"))
      (node (ref "R_E2_1") (pin "2") (pinfunction "2_2") (pintype "passive"))
      (node (ref "R_E2_2") (pin "1") (pinfunction "1_1") (pintype "passive"))
    )
    (net (code "13") (name "/A11") (class "Default")
      (node (ref "IC4") (pin "86") (pinfunction "PK3(ADC11/PCINT19)_86") (pintype "bidirectional"))
    )
    (net (code "14") (name "/A12") (class "Default")
      (node (ref "IC4") (pin "85") (pinfunction "PK4(ADC12/PCINT20)_85") (pintype "bidirectional"))
      (node (ref "TX1") (pin "2") (pinfunction "2_2") (pintype "passive"))
    )
    (net (code "15") (name "/A13") (class "Default")
      (node (ref "IC4") (pin "84") (pinfunction "PK5(ADC13/PCINT21)_84") (pintype "bidirectional"))
      (node (ref "R_BL_L1") (pin "1") (pinfunction "1_1") (pintype "passive"))
      (node (ref "TX1") (pin "1") (pinfunction "1_1") (pintype "passive"))
      (node (ref "TX2") (pin "1") (pinfunction "1_1") (pintype "passive"))
    )
    (net (code "16") (name "/A14") (class "Default")
      (node (ref "IC4") (pin "83") (pinfunction "PK6(ADC14/PCINT22)_83") (pintype "bidirectional"))
    )
    (net (code "17") (name "/A15") (class "Default")
      (node (ref "IC4") (pin "82") (pinfunction "PK7(ADC15/PCINT23)_82") (pintype "bidirectional"))
    )
    (net (code "18") (name "/ANT") (class "Default")
      (node (ref "BLUETOOTH") (pin "P$37") (pinfunction "P$37_RF-IO-ANTENNA_P$37") (pintype "bidirectional"))
    )
    (net (code "19") (name "/ARD_RES_OUT") (class "Default")
      (node (ref "C35") (pin "1") (pinfunction "1_1") (pintype "passive"))
      (node (ref "IC4") (pin "30") (pinfunction "RESET_30") (pintype "input"))
      (node (ref "JP1") (pin "2") (pinfunction "2_2") (pintype "passive"))
      (node (ref "R_RES_UP") (pin "1") (pinfunction "1_1") (pintype "passive"))
      (node (ref "S1") (pin "4") (pinfunction "2_4") (pintype "passive"))
      (node (ref "U$1") (pin "28") (pinfunction "(ADC5/PCINT13/SCL)PC5_28") (pintype "output"))
    )
    (net (code "20") (name "/ARD_RX_5") (class "Default")
      (node (ref "RX_H") (pin "1") (pinfunction "1_1") (pintype "passive"))
      (node (ref "TX") (pin "1") (pinfunction "1_1") (pintype "passive"))
    )
    (net (code "21") (name "/ARD_RX_33") (class "Default")
      (node (ref "BLUETOOTH") (pin "P$26") (pinfunction "P$26UART-RX_P$26") (pintype "input"))
      (node (ref "RX_H") (pin "2") (pinfunction "2_2") (pintype "passive"))
      (node (ref "RX_L") (pin "2") (pinfunction "2_2") (pintype "passive"))
    )
    (net (code "22") (name "/BAT+") (class "Default")
      (node (ref "3.3V_SUPPLY") (pin "IN") (pinfunction "IN_IN") (pintype "bidirectional"))
      (node (ref "5V_SUPPLY") (pin "IN") (pinfunction "IN_IN") (pintype "bidirectional"))
      (node (ref "C11") (pin "1") (pinfunction "1_1") (pintype "passive"))
      (node (ref "CP3") (pin "POS") (pinfunction "PLUS_POS") (pintype "power_in"))
      (node (ref "CP4") (pin "POS") (pinfunction "PLUS_POS") (pintype "power_in"))
      (node (ref "L8") (pin "2") (pinfunction "2_2") (pintype "passive"))
    )
    (net (code "23") (name "/BL_L_IN") (class "Default")
      (node (ref "D2") (pin "3") (pinfunction "C_3") (pintype "passive"))
      (node (ref "IC4") (pin "8") (pinfunction "(T3/INT6)PE6_8") (pintype "bidirectional"))
      (node (ref "R_FLASHL") (pin "2") (pinfunction "2_2") (pintype "passive"))
      (node (ref "R_FLASHL_DOWN") (pin "1") (pinfunction "1_1") (pintype "passive"))
    )
    (net (code "24") (name "/BL_L_IN_H") (class "Default")
      (node (ref "R_FLASHL") (pin "1") (pinfunction "1_1") (pintype "passive"))
      (node (ref "SPEEDOSTECKER") (pin "P$10") (pinfunction "FLASH_L_P$10") (pintype "input"))
    )
    (net (code "25") (name "/BL_R_IN") (class "Default")
      (node (ref "D1") (pin "3") (pinfunction "C_3") (pintype "passive"))
      (node (ref "IC4") (pin "9") (pinfunction "(CLKO/ICP3/INT7)PE7_9") (pintype "bidirectional"))
      (node (ref "R_FLASHR") (pin "2") (pinfunction "2_2") (pintype "passive"))
      (node (ref "R_FLASHR_DOWN") (pin "1") (pinfunction "1_1") (pintype "passive"))
    )
    (net (code "26") (name "/BL_R_IN_H") (class "Default")
      (node (ref "R_FLASHR") (pin "1") (pinfunction "1_1") (pintype "passive"))
      (node (ref "SPEEDOSTECKER") (pin "P$4") (pinfunction "FLASH_R_P$4") (pintype "input"))
    )
    (net (code "27") (name "/B_DOWN") (class "Default")
      (node (ref "B_DOWN") (pin "OUT") (pinfunction "OUT_OUT") (pintype "bidirectional"))
      (node (ref "IC4") (pin "68") (pinfunction "PJ5(PCINT14)_68") (pintype "bidirectional"))
    )
    (net (code "28") (name "/B_LEFT") (class "Default")
      (node (ref "B_LEFT") (pin "OUT") (pinfunction "OUT_OUT") (pintype "bidirectional"))
      (node (ref "D12") (pin "3") (pinfunction "C_3") (pintype "passive"))
      (node (ref "D14") (pin "3") (pinfunction "C_3") (pintype "passive"))
    )
    (net (code "29") (name "/B_RIGHT") (class "Default")
      (node (ref "B_RIGHT") (pin "OUT") (pinfunction "OUT_OUT") (pintype "bidirectional"))
      (node (ref "IC4") (pin "69") (pinfunction "PJ6(PCINT15)_69") (pintype "bidirectional"))
    )
    (net (code "30") (name "/B_UP") (class "Default")
      (node (ref "B_UP") (pin "OUT") (pinfunction "OUT_OUT") (pintype "bidirectional"))
      (node (ref "IC4") (pin "66") (pinfunction "PJ3(PCINT12)_66") (pintype "bidirectional"))
    )
    (net (code "31") (name "/CONNECT") (class "Default")
      (node (ref "BLUETOOTH") (pin "P$13") (pinfunction "P$13_PIO(7)_P$13") (pintype "bidirectional"))
      (node (ref "R_CNT") (pin "2") (pinfunction "2_2") (pintype "passive"))
      (node (ref "U$1") (pin "32") (pinfunction "(INT0/PCINT18)PD2_32") (pintype "bidirectional"))
    )
    (net (code "32") (name "/D2") (class "Default")
      (node (ref "IC1") (pin "3") (pinfunction "O_3") (pintype "output"))
      (node (ref "IC4") (pin "6") (pinfunction "(OC3B/INT4)PE4_6") (pintype "bidirectional"))
    )
    (net (code "33") (name "/D3") (class "Default")
      (node (ref "IC1") (pin "11") (pinfunction "O_11") (pintype "output"))
      (node (ref "IC4") (pin "7") (pinfunction "(OC3C/INT5)PE5_7") (pintype "bidirectional"))
    )
    (net (code "34") (name "/D4") (class "Default")
      (node (ref "IC4") (pin "1") (pinfunction "(OC0B)PG5_1") (pintype "bidirectional"))
      (node (ref "R_SD_PWR_UP") (pin "2") (pinfunction "2_2") (pintype "passive"))
      (node (ref "T_P_BRIDGE1") (pin "1") (pinfunction "G_1") (pintype "passive"))
    )
    (net (code "35") (name "/D5") (class "Default")
      (node (ref "IC4") (pin "5") (pinfunction "(OC3A/AIN1)PE3_5") (pintype "bidirectional"))
    )
    (net (code "36") (name "/D6") (class "Default")
      (node (ref "IC4") (pin "15") (pinfunction "PH3(OC4A)_15") (pintype "bidirectional"))
      (node (ref "U$1") (pin "1") (pinfunction "(PCINT19/OC2B/INT1)PD3_1") (pintype "bidirectional"))
    )
    (net (code "37") (name "/D7") (class "Default")
      (node (ref "IC4") (pin "16") (pinfunction "PH4(OC4B)_16") (pintype "bidirectional"))
      (node (ref "R_B_LED_15") (pin "1") (pinfunction "1_1") (pintype "passive"))
      (node (ref "T12") (pin "1") (pinfunction "G_1") (pintype "passive"))
      (node (ref "T3") (pin "1") (pinfunction "G_1") (pintype "passive"))
    )
    (net (code "38") (name "/D8") (class "Default")
      (node (ref "IC4") (pin "17") (pinfunction "PH5(OC4C)_17") (pintype "bidirectional"))
      (node (ref "R_B_LED_14") (pin "1") (pinfunction "1_1") (pintype "passive"))
      (node (ref "T2") (pin "1") (pinfunction "G_1") (pintype "passive"))
    )
    (net (code "39") (name "/D9") (class "Default")
      (node (ref "IC4") (pin "18") (pinfunction "PH6(OC2B)_18") (pintype "bidirectional"))
      (node (ref "R_B_LED_13") (pin "1") (pinfunction "1_1") (pintype "passive"))
      (node (ref "T1") (pin "1") (pinfunction "G_1") (pintype "passive"))
    )
    (net (code "40") (name "/D10") (class "Default")
      (node (ref "IC4") (pin "23") (pinfunction "(OC2A/PCINT4)PB4_23") (pintype "bidirectional"))
    )
    (net (code "41") (name "/D11") (class "Default")
      (node (ref "IC4") (pin "24") (pinfunction "(OC1A/PCINT5)PB5_24") (pintype "bidirectional"))
    )
    (net (code "42") (name "/D12") (class "Default")
      (node (ref "D7") (pin "1") (pinfunction "A_1") (pintype "passive"))
      (node (ref "IC4") (pin "25") (pinfunction "(OC1B/PCINT6)PB6_25") (pintype "bidirectional"))
    )
    (net (code "43") (name "/D13") (class "Default")
      (node (ref "IC4") (pin "26") (pinfunction "(OC0A/OC1C/PCINT7)PB7_26") (pintype "bidirectional"))
      (node (ref "R_B_LED_12") (pin "1") (pinfunction "1_1") (pintype "passive"))
      (node (ref "T11") (pin "1") (pinfunction "G_1") (pintype "passive"))
    )
    (net (code "44") (name "/D22") (class "Default")
      (node (ref "IC4") (pin "78") (pinfunction "(AD0)PA0_78") (pintype "bidirectional"))
    )
    (net (code "45") (name "/D23") (class "Default")
      (node (ref "IC4") (pin "77") (pinfunction "(AD1)PA1_77") (pintype "bidirectional"))
    )
    (net (code "46") (name "/D24") (class "Default")
      (node (ref "IC4") (pin "76") (pinfunction "(AD2)PA2_76") (pintype "bidirectional"))
    )
    (net (code "47") (name "/D25") (class "Default")
      (node (ref "IC4") (pin "75") (pinfunction "(AD3)PA3_75") (pintype "bidirectional"))
    )
    (net (code "48") (name "/D26") (class "Default")
      (node (ref "IC4") (pin "74") (pinfunction "(AD4)PA4_74") (pintype "bidirectional"))
    )
    (net (code "49") (name "/D27") (class "Default")
      (node (ref "IC4") (pin "73") (pinfunction "(AD5)PA5_73") (pintype "bidirectional"))
    )
    (net (code "50") (name "/D28") (class "Default")
      (node (ref "IC4") (pin "72") (pinfunction "(AD6)PA6_72") (pintype "bidirectional"))
    )
    (net (code "51") (name "/D29") (class "Default")
      (node (ref "IC4") (pin "71") (pinfunction "(AD7)PA7_71") (pintype "bidirectional"))
    )
    (net (code "52") (name "/D30") (class "Default")
      (node (ref "IC4") (pin "60") (pinfunction "(A15)PC7_60") (pintype "bidirectional"))
      (node (ref "NHD_2.7") (pin "DC") (pinfunction "DC_DC") (pintype "bidirectional"))
    )
    (net (code "53") (name "/D31") (class "Default")
      (node (ref "IC4") (pin "59") (pinfunction "(A14)PC6_59") (pintype "bidirectional"))
    )
    (net (code "54") (name "/D32") (class "Default")
      (node (ref "IC4") (pin "58") (pinfunction "(A13)PC5_58") (pintype "bidirectional"))
      (node (ref "NHD_2.7") (pin "RES") (pinfunction "RES_RES") (pintype "bidirectional"))
    )
    (net (code "55") (name "/D33") (class "Default")
      (node (ref "IC4") (pin "57") (pinfunction "(A12)PC4_57") (pintype "bidirectional"))
    )
    (net (code "56") (name "/D34") (class "Default")
      (node (ref "IC4") (pin "56") (pinfunction "(A11)PC3_56") (pintype "bidirectional"))
      (node (ref "NHD_2.7") (pin "CS") (pinfunction "CS_CS") (pintype "bidirectional"))
    )
    (net (code "57") (name "/D36") (class "Default")
      (node (ref "IC4") (pin "54") (pinfunction "(A9)PC1_54") (pintype "bidirectional"))
      (node (ref "NHD_2.7") (pin "SDIN") (pinfunction "SDA_SDIN") (pintype "bidirectional"))
    )
    (net (code "58") (name "/D38") (class "Default")
      (node (ref "IC4") (pin "50") (pinfunction "(T0)PD7_50") (pintype "bidirectional"))
    )
    (net (code "59") (name "/D39") (class "Default")
      (node (ref "IC4") (pin "70") (pinfunction "(ALE)PG2_70") (pintype "bidirectional"))
    )
    (net (code "60") (name "/D42") (class "Default")
      (node (ref "IC4") (pin "42") (pinfunction "PL7_42") (pintype "bidirectional"))
    )
    (net (code "61") (name "/D43") (class "Default")
      (node (ref "IC4") (pin "41") (pinfunction "PL6_41") (pintype "bidirectional"))
    )
    (net (code "62") (name "/D44") (class "Default")
      (node (ref "IC4") (pin "40") (pinfunction "PL5(OC5C)_40") (pintype "bidirectional"))
    )
    (net (code "63") (name "/D45") (class "Default")
      (node (ref "IC4") (pin "39") (pinfunction "PL4(OC5B)_39") (pintype "bidirectional"))
    )
    (net (code "64") (name "/D46") (class "Default")
      (node (ref "IC4") (pin "38") (pinfunction "PL3(OC5A)_38") (pintype "bidirectional"))
    )
    (net (code "65") (name "/D47") (class "Default")
      (node (ref "IC4") (pin "37") (pinfunction "PL2(T5)_37") (pintype "bidirectional"))
      (node (ref "R_E1_2") (pin "2") (pinfunction "2_2") (pintype "passive"))
      (node (ref "R_E1_4") (pin "2") (pinfunction "2_2") (pintype "passive"))
    )
    (net (code "66") (name "/D48") (class "Default")
      (node (ref "D_P_MCCOI") (pin "3") (pinfunction "C_3") (pintype "passive"))
      (node (ref "IC4") (pin "36") (pinfunction "PL1(ICP5)_36") (pintype "bidirectional"))
      (node (ref "R_HB4") (pin "2") (pinfunction "2_2") (pintype "passive"))
    )
    (net (code "67") (name "/D50") (class "Default")
      (node (ref "IC4") (pin "22") (pinfunction "(MISO/PCINT3)PB3_22") (pintype "bidirectional"))
      (node (ref "JP1") (pin "6") (pinfunction "6_6") (pintype "passive"))
      (node (ref "ST2") (pin "7") (pinfunction "DAT0_7") (pintype "bidirectional"))
    )
    (net (code "68") (name "/D51") (class "Default")
      (node (ref "IC4") (pin "21") (pinfunction "(MOSI/PCINT2)PB2_21") (pintype "bidirectional"))
      (node (ref "JP1") (pin "3") (pinfunction "3_3") (pintype "passive"))
      (node (ref "U$14") (pin "7") (pinfunction "A5_7") (pintype "bidirectional"))
    )
    (net (code "69") (name "/D52") (class "Default")
      (node (ref "IC4") (pin "20") (pinfunction "(SCK/PCINT1)PB1_20") (pintype "bidirectional"))
      (node (ref "JP1") (pin "4") (pinfunction "4_4") (pintype "passive"))
      (node (ref "U$14") (pin "8") (pinfunction "A6_8") (pintype "bidirectional"))
    )
    (net (code "70") (name "/D53") (class "Default")
      (node (ref "IC4") (pin "19") (pinfunction "(SS/PCINT0)PB0_19") (pintype "bidirectional"))
      (node (ref "U$14") (pin "9") (pinfunction "A7_9") (pintype "bidirectional"))
    )
    (net (code "71") (name "/DISP_SCL") (class "Default")
      (node (ref "IC4") (pin "55") (pinfunction "(A10)PC2_55") (pintype "bidirectional"))
      (node (ref "NHD_2.7") (pin "SCLK") (pinfunction "SCL_SCLK") (pintype "bidirectional"))
    )
    (net (code "72") (name "/DZ") (class "Default")
      (node (ref "C8") (pin "1") (pinfunction "1_1") (pintype "passive"))
      (node (ref "D6") (pin "3") (pinfunction "C_3") (pintype "passive"))
      (node (ref "IC1") (pin "2") (pinfunction "I1_2") (pintype "input"))
      (node (ref "R_DZ") (pin "2") (pinfunction "2_2") (pintype "passive"))
      (node (ref "R_DZ_DOWN") (pin "1") (pinfunction "1_1") (pintype "passive"))
    )
    (net (code "73") (name "/DZ_IN") (class "Default")
      (node (ref "R_DZ") (pin "1") (pinfunction "1_1") (pintype "passive"))
      (node (ref "SPEEDOSTECKER") (pin "P$6") (pinfunction "DZ_P$6") (pintype "input"))
    )
    (net (code "74") (name "/HB_IN") (class "Default")
      (node (ref "D8") (pin "3") (pinfunction "C_3") (pintype "passive"))
      (node (ref "IC4") (pin "87") (pinfunction "PK2(ADC10/PCINT18)_87") (pintype "bidirectional"))
      (node (ref "R_HB") (pin "2") (pinfunction "2_2") (pintype "passive"))
      (node (ref "R_HB_DOWN") (pin "1") (pinfunction "1_1") (pintype "passive"))
    )
    (net (code "75") (name "/HB_IN_H") (class "Default")
      (node (ref "R_HB") (pin "1") (pinfunction "1_1") (pintype "passive"))
      (node (ref "SPEEDOSTECKER") (pin "P$1") (pinfunction "HIGH_BEAM_P$1") (pintype "input"))
    )
    (net (code "76") (name "/KUPPLUNG_IN") (class "Default")
      (node (ref "D7") (pin "3") (pinfunction "C_3") (pintype "passive"))
      (node (ref "SPEEDOSTECKER") (pin "P$8") (pinfunction "KUPPLUNG_IN_P$8") (pintype "input"))
    )
    (net (code "77") (name "/M1") (class "Default")
      (node (ref "STEPPER") (pin "1+") (pinfunction "1+_1+") (pintype "bidirectional"))
      (node (ref "U$1") (pin "23") (pinfunction "(ADC0/PCINT8)PC0_23") (pintype "output"))
    )
    (net (code "78") (name "/M2") (class "Default")
      (node (ref "STEPPER") (pin "1-") (pinfunction "1-_1-") (pintype "bidirectional"))
      (node (ref "U$1") (pin "24") (pinfunction "(ADC1/PCINT9)PC1_24") (pintype "output"))
    )
    (net (code "79") (name "/M3") (class "Default")
      (node (ref "STEPPER") (pin "2+") (pinfunction "2+_2+") (pintype "bidirectional"))
      (node (ref "U$1") (pin "25") (pinfunction "(ADC2/PCINT10)PC2_25") (pintype "output"))
    )
    (net (code "80") (name "/M4") (class "Default")
      (node (ref "STEPPER") (pin "2-") (pinfunction "2-_2-") (pintype "bidirectional"))
      (node (ref "U$1") (pin "26") (pinfunction "(ADC3/PCINT11)PC3_26") (pintype "output"))
    )
    (net (code "81") (name "/MISO_AT8") (class "Default")
      (node (ref "JP2") (pin "6") (pinfunction "6_6") (pintype "passive"))
      (node (ref "U$1") (pin "16") (pinfunction "(PCINT4/MISO)PB4_16") (pintype "bidirectional"))
    )
    (net (code "82") (name "/MOSI_AT8") (class "Default")
      (node (ref "JP2") (pin "3") (pinfunction "3_3") (pintype "passive"))
      (node (ref "U$1") (pin "15") (pinfunction "(PCINT3/OC2A/MOSI)PB3_15") (pintype "bidirectional"))
    )
    (net (code "83") (name "/N$44") (class "Default")
      (node (ref "IC4") (pin "53") (pinfunction "(A8)PC0_53") (pintype "bidirectional"))
    )
    (net (code "84") (name "/N$48") (class "Default")
      (node (ref "IC4") (pin "52") (pinfunction "(RD)PG1_52") (pintype "bidirectional"))
    )
    (net (code "85") (name "/N$70") (class "Default")
      (node (ref "R_HB1") (pin "1") (pinfunction "1_1") (pintype "passive"))
      (node (ref "SPEEDOSTECKER") (pin "P$3") (pinfunction "OIL_PRESSURE_P$3") (pintype "input"))
    )
    (net (code "86") (name "/N$110") (class "Default")
      (node (ref "R_HB5") (pin "1") (pinfunction "1_1") (pintype "passive"))
      (node (ref "SPEEDOSTECKER") (pin "P$5") (pinfunction "NEUTRAL_GEAR_P$5") (pintype "input"))
    )
    (net (code "87") (name "/NG_IN") (class "Default")
      (node (ref "D10") (pin "3") (pinfunction "C_3") (pintype "passive"))
      (node (ref "IC4") (pin "88") (pinfunction "PK1(ADC9/PCINT17)_88") (pintype "bidirectional"))
      (node (ref "R_HB5") (pin "2") (pinfunction "2_2") (pintype "passive"))
    )
    (net (code "88") (name "/OIL_PR_IN") (class "Default")
      (node (ref "D21") (pin "3") (pinfunction "C_3") (pintype "passive"))
      (node (ref "IC4") (pin "89") (pinfunction "PK0(ADC8/PCINT16)_89") (pintype "bidirectional"))
      (node (ref "R_HB1") (pin "2") (pinfunction "2_2") (pintype "passive"))
    )
    (net (code "89") (name "/PE_A3") (class "Default")
      (node (ref "R_B_LED_17") (pin "2") (pinfunction "2_2") (pintype "passive"))
      (node (ref "T9") (pin "1") (pinfunction "G_1") (pintype "passive"))
      (node (ref "U$19") (pin "24") (pinfunction "A3_24") (pintype "bidirectional"))
    )
    (net (code "90") (name "/PE_A4") (class "Default")
      (node (ref "R_B_LED_19") (pin "2") (pinfunction "2_2") (pintype "passive"))
      (node (ref "T7") (pin "1") (pinfunction "G_1") (pintype "passive"))
      (node (ref "U$19") (pin "25") (pinfunction "A4_25") (pintype "bidirectional"))
    )
    (net (code "91") (name "/PE_A5") (class "Default")
      (node (ref "R_B_LED_20") (pin "2") (pinfunction "2_2") (pintype "passive"))
      (node (ref "T6") (pin "1") (pinfunction "G_1") (pintype "passive"))
      (node (ref "U$19") (pin "26") (pinfunction "A5_26") (pintype "bidirectional"))
    )
    (net (code "92") (name "/PE_A6") (class "Default")
      (node (ref "R_B_LED_16") (pin "2") (pinfunction "2_2") (pintype "passive"))
      (node (ref "T10") (pin "1") (pinfunction "G_1") (pintype "passive"))
      (node (ref "U$19") (pin "27") (pinfunction "A6_27") (pintype "bidirectional"))
    )
    (net (code "93") (name "/PE_A7") (class "Default")
      (node (ref "R_B_LED_18") (pin "2") (pinfunction "2_2") (pintype "passive"))
      (node (ref "T8") (pin "1") (pinfunction "G_1") (pintype "passive"))
      (node (ref "U$19") (pin "28") (pinfunction "A7_28") (pintype "bidirectional"))
    )
    (net (code "94") (name "/REED_IN") (class "Default")
      (node (ref "R_REED") (pin "1") (pinfunction "1_1") (pintype "passive"))
      (node (ref "SPEEDOSTECKER") (pin "P$9") (pinfunction "REED_P$9") (pintype "input"))
    )
    (net (code "95") (name "/RESETAVR_AT8") (class "Default")
      (node (ref "C9") (pin "1") (pinfunction "1_1") (pintype "passive"))
      (node (ref "IC4") (pin "47") (pinfunction "(ICP1)PD4_47") (pintype "bidirectional"))
      (node (ref "JP2") (pin "2") (pinfunction "2_2") (pintype "passive"))
      (node (ref "R_L3") (pin "2") (pinfunction "2_2") (pintype "passive"))
      (node (ref "U$1") (pin "29") (pinfunction "(~{RESET}/PCINT14)PC6_29") (pintype "output"))
    )
    (net (code "96") (name "/RX0") (class "Default")
      (node (ref "IC4") (pin "2") (pinfunction "(RXD0/PCIN8)PE0_2") (pintype "bidirectional"))
      (node (ref "RX") (pin "1") (pinfunction "1_1") (pintype "passive"))
    )
    (net (code "97") (name "/RX1") (class "Default")
      (node (ref "GPS") (pin "TXD") (pinfunction "TXD_NMEA_OUT_TXD") (pintype "bidirectional"))
      (node (ref "IC4") (pin "45") (pinfunction "(RXD1/INT2)PD2_45") (pintype "bidirectional"))
    )
    (net (code "98") (name "/RX3") (class "Default")
      (node (ref "IC4") (pin "63") (pinfunction "PJ0(RXD3/PCINT9)_63") (pintype "bidirectional"))
      (node (ref "U$1") (pin "31") (pinfunction "(TXD/PCINT17)PD1_31") (pintype "bidirectional"))
    )
    (net (code "99") (name "/SCK_AT8") (class "Default")
      (node (ref "JP2") (pin "4") (pinfunction "4_4") (pintype "passive"))
      (node (ref "U$1") (pin "17") (pinfunction "(PCINT5/SCK)PB5_17") (pintype "bidirectional"))
    )
    (net (code "100") (name "/SCL") (class "Default")
      (node (ref "IC4") (pin "43") (pinfunction "(SCL/INT0)PD0_43") (pintype "bidirectional"))
      (node (ref "R_SCL_UP") (pin "2") (pinfunction "2_2") (pintype "passive"))
      (node (ref "TEMP_SENS") (pin "2") (pinfunction "SCL_2") (pintype "bidirectional"))
      (node (ref "TX2") (pin "3") (pinfunction "3_3") (pintype "passive"))
      (node (ref "U$19") (pin "12") (pinfunction "SCL_12") (pintype "bidirectional"))
    )
    (net (code "101") (name "/SDA") (class "Default")
      (node (ref "IC4") (pin "44") (pinfunction "(SDA/INT1)PD1_44") (pintype "bidirectional"))
      (node (ref "R_SDA_UP") (pin "2") (pinfunction "2_2") (pintype "passive"))
      (node (ref "TEMP_SENS") (pin "1") (pinfunction "SDA_1") (pintype "bidirectional"))
      (node (ref "TX2") (pin "2") (pinfunction "2_2") (pintype "passive"))
      (node (ref "U$19") (pin "13") (pinfunction "SDA_13") (pintype "bidirectional"))
    )
    (net (code "102") (name "/SD_CD") (class "Default")
      (node (ref "ST2") (pin "2") (pinfunction "DAT3/CD_2") (pintype "bidirectional"))
      (node (ref "U$14") (pin "11") (pinfunction "B7_11") (pintype "bidirectional"))
    )
    (net (code "103") (name "/SD_CLK") (class "Default")
      (node (ref "ST2") (pin "5") (pinfunction "CLK_5") (pintype "bidirectional"))
      (node (ref "U$14") (pin "12") (pinfunction "B6_12") (pintype "bidirectional"))
    )
    (net (code "104") (name "/SD_DATA_IN") (class "Default")
      (node (ref "ST2") (pin "3") (pinfunction "CMD_3") (pintype "bidirectional"))
      (node (ref "U$14") (pin "13") (pinfunction "B5_13") (pintype "bidirectional"))
    )
    (net (code "105") (name "/SELF_PWR_UP") (class "Default")
      (node (ref "IC4") (pin "35") (pinfunction "PL0(ICP4)_35") (pintype "bidirectional"))
      (node (ref "R_DEAKT_DAUER_P1") (pin "1") (pinfunction "1_1") (pintype "passive"))
      (node (ref "T13") (pin "1") (pinfunction "G_1") (pintype "passive"))
    )
    (net (code "106") (name "/TX") (class "Default")
      (node (ref "BLUETOOTH") (pin "P$27") (pinfunction "P$27_UART-TX_P$27") (pintype "output"))
      (node (ref "RX") (pin "2") (pinfunction "2_2") (pintype "passive"))
    )
    (net (code "107") (name "/TX0") (class "Default")
      (node (ref "IC4") (pin "3") (pinfunction "(TXD0)PE1_3") (pintype "bidirectional"))
      (node (ref "TX") (pin "2") (pinfunction "2_2") (pintype "passive"))
    )
    (net (code "108") (name "/TX1") (class "Default")
      (node (ref "IC4") (pin "46") (pinfunction "(TXD1/INT3)PD3_46") (pintype "bidirectional"))
      (node (ref "R_TX_UP") (pin "2") (pinfunction "2_2") (pintype "passive"))
    )
    (net (code "109") (name "/TX1_3.3") (class "Default")
      (node (ref "GPS") (pin "RXD") (pinfunction "RXD_RXD") (pintype "bidirectional"))
      (node (ref "R_TX_DOWN") (pin "1") (pinfunction "1_1") (pintype "passive"))
      (node (ref "R_TX_UP") (pin "1") (pinfunction "1_1") (pintype "passive"))
    )
    (net (code "110") (name "/TX3") (class "Default")
      (node (ref "IC4") (pin "64") (pinfunction "PJ1(TXD3/PCINT10)_64") (pintype "bidirectional"))
      (node (ref "U$1") (pin "30") (pinfunction "(RXD/PCINT16)PD0_30") (pintype "bidirectional"))
    )
    (net (code "111") (name "/V_AT8_BUFFERED") (class "Default")
      (node (ref "AT8_REF") (pin "1") (pinfunction "1_1") (pintype "passive"))
      (node (ref "C2") (pin "2") (pinfunction "2_2") (pintype "passive"))
      (node (ref "C3") (pin "2") (pinfunction "2_2") (pintype "passive"))
      (node (ref "C_EMERGENCY") (pin "PLUS") (pinfunction "PLUS_PLUS") (pintype "power_in"))
      (node (ref "D9") (pin "C") (pinfunction "C_C") (pintype "passive"))
      (node (ref "JP2") (pin "5") (pinfunction "5_5") (pintype "passive"))
      (node (ref "U$1") (pin "4") (pinfunction "VCC_4") (pintype "power_in"))
      (node (ref "U$1") (pin "6") (pinfunction "VCC_6") (pintype "power_in"))
    )
    (net (code "112") (name "GND") (class "Default")
      (node (ref "3.3V_SUPPLY") (pin "GND") (pinfunction "GND_GND") (pintype "bidirectional"))
      (node (ref "5V_SUPPLY") (pin "GND") (pinfunction "GND_GND") (pintype "bidirectional"))
      (node (ref "BLUETOOTH") (pin "P$1") (pinfunction "P$1_GND_P$1") (pintype "power_in"))
      (node (ref "BLUETOOTH") (pin "P$10") (pinfunction "P$10_GND_P$10") (pintype "power_in"))
      (node (ref "BLUETOOTH") (pin "P$18") (pinfunction "P$18_GND_P$18") (pintype "power_in"))
      (node (ref "BLUETOOTH") (pin "P$19") (pinfunction "P$19_GND_P$19") (pintype "power_in"))
      (node (ref "BLUETOOTH") (pin "P$29") (pinfunction "P$29_GND_P$29") (pintype "power_in"))
      (node (ref "BLUETOOTH") (pin "P$38") (pinfunction "P$38_GND_P$38") (pintype "power_in"))
      (node (ref "BLUETOOTH") (pin "P$AGND") (pinfunction "P$AGND_P$AGND") (pintype "power_in"))
      (node (ref "BLUETOOTH") (pin "P$BGND") (pinfunction "P$BGND_P$BGND") (pintype "power_in"))
      (node (ref "B_DOWN") (pin "IN") (pinfunction "IN_IN") (pintype "bidirectional"))
      (node (ref "B_DOWN") (pin "IN2") (pinfunction "IN_IN2") (pintype "bidirectional"))
      (node (ref "B_LEFT") (pin "IN") (pinfunction "IN_IN") (pintype "bidirectional"))
      (node (ref "B_LEFT") (pin "IN2") (pinfunction "IN_IN2") (pintype "bidirectional"))
      (node (ref "B_RIGHT") (pin "IN") (pinfunction "IN_IN") (pintype "bidirectional"))
      (node (ref "B_RIGHT") (pin "IN2") (pinfunction "IN_IN2") (pintype "bidirectional"))
      (node (ref "B_UP") (pin "IN") (pinfunction "IN_IN") (pintype "bidirectional"))
      (node (ref "B_UP") (pin "IN2") (pinfunction "IN_IN2") (pintype "bidirectional"))
      (node (ref "C1") (pin "2") (pinfunction "2_2") (pintype "passive"))
      (node (ref "C10") (pin "1") (pinfunction "1_1") (pintype "passive"))
      (node (ref "C11") (pin "2") (pinfunction "2_2") (pintype "passive"))
      (node (ref "C12") (pin "1") (pinfunction "1_1") (pintype "passive"))
      (node (ref "C13") (pin "1") (pinfunction "1_1") (pintype "passive"))
      (node (ref "C18") (pin "2") (pinfunction "2_2") (pintype "passive"))
      (node (ref "C19") (pin "1") (pinfunction "1_1") (pintype "passive"))
      (node (ref "C2") (pin "1") (pinfunction "1_1") (pintype "passive"))
      (node (ref "C3") (pin "1") (pinfunction "1_1") (pintype "passive"))
      (node (ref "C31") (pin "2") (pinfunction "2_2") (pintype "passive"))
      (node (ref "C32") (pin "2") (pinfunction "2_2") (pintype "passive"))
      (node (ref "C33") (pin "2") (pinfunction "2_2") (pintype "passive"))
      (node (ref "C34") (pin "2") (pinfunction "2_2") (pintype "passive"))
      (node (ref "C35") (pin "2") (pinfunction "2_2") (pintype "passive"))
      (node (ref "C36") (pin "1") (pinfunction "1_1") (pintype "passive"))
      (node (ref "C39") (pin "2") (pinfunction "2_2") (pintype "passive"))
      (node (ref "C4") (pin "1") (pinfunction "1_1") (pintype "passive"))
      (node (ref "C5") (pin "2") (pinfunction "2_2") (pintype "passive"))
      (node (ref "C6") (pin "2") (pinfunction "2_2") (pintype "passive"))
      (node (ref "C7") (pin "2") (pinfunction "2_2") (pintype "passive"))
      (node (ref "C8") (pin "2") (pinfunction "2_2") (pintype "passive"))
      (node (ref "C9") (pin "2") (pinfunction "2_2") (pintype "passive"))
      (node (ref "CP1") (pin "NEG") (pinfunction "GND_NEG") (pintype "power_in"))
      (node (ref "CP2") (pin "NEG") (pinfunction "GND_NEG") (pintype "power_in"))
      (node (ref "CP3") (pin "NEG") (pinfunction "GND_NEG") (pintype "power_in"))
      (node (ref "CP4") (pin "NEG") (pinfunction "GND_NEG") (pintype "power_in"))
      (node (ref "C_EMERGENCY") (pin "MINUS") (pinfunction "GND_MINUS") (pintype "power_in"))
      (node (ref "C_QUA_4") (pin "1") (pinfunction "1_1") (pintype "passive"))
      (node (ref "C_QUA_5") (pin "1") (pinfunction "1_1") (pintype "passive"))
      (node (ref "D1") (pin "1") (pinfunction "A_1") (pintype "passive"))
      (node (ref "D10") (pin "1") (pinfunction "A_1") (pintype "passive"))
      (node (ref "D13") (pin "1") (pinfunction "A_1") (pintype "passive"))
      (node (ref "D18") (pin "1") (pinfunction "A_1") (pintype "passive"))
      (node (ref "D2") (pin "1") (pinfunction "A_1") (pintype "passive"))
      (node (ref "D20") (pin "1") (pinfunction "A_1") (pintype "passive"))
      (node (ref "D21") (pin "1") (pinfunction "A_1") (pintype "passive"))
      (node (ref "D22") (pin "1") (pinfunction "A_1") (pintype "passive"))
      (node (ref "D3") (pin "1") (pinfunction "A_1") (pintype "passive"))
      (node (ref "D4") (pin "2") (pinfunction "K_2") (pintype "passive"))
      (node (ref "D5") (pin "2") (pinfunction "K_2") (pintype "passive"))
      (node (ref "D6") (pin "1") (pinfunction "A_1") (pintype "passive"))
      (node (ref "D8") (pin "1") (pinfunction "A_1") (pintype "passive"))
      (node (ref "D_GPS_FIX") (pin "2") (pinfunction "K_2") (pintype "passive"))
      (node (ref "D_L0") (pin "2") (pinfunction "K_2") (pintype "passive"))
      (node (ref "D_L1") (pin "2") (pinfunction "K_2") (pintype "passive"))
      (node (ref "D_L2") (pin "2") (pinfunction "K_2") (pintype "passive"))
      (node (ref "D_PWR_LED") (pin "2") (pinfunction "K_2") (pintype "passive"))
      (node (ref "D_P_MCCOI") (pin "1") (pinfunction "A_1") (pintype "passive"))
      (node (ref "GPS") (pin "GND") (pinfunction "GND_GND") (pintype "bidirectional"))
      (node (ref "GPS") (pin "GND2") (pinfunction "GND2_GND2") (pintype "bidirectional"))
      (node (ref "GPS") (pin "GND_3") (pinfunction "GND_3_GND_3") (pintype "bidirectional"))
      (node (ref "GPS") (pin "GND_4") (pinfunction "GND_4_GND_4") (pintype "bidirectional"))
      (node (ref "GPS") (pin "GND_5") (pinfunction "GND_5_GND_5") (pintype "bidirectional"))
      (node (ref "GPS_BAT") (pin "GND") (pinfunction "-_GND") (pintype "power_in"))
      (node (ref "GPS_C1") (pin "1") (pinfunction "1_1") (pintype "passive"))
      (node (ref "GPS_C2") (pin "2") (pinfunction "2_2") (pintype "passive"))
      (node (ref "GPS_C3") (pin "1") (pinfunction "1_1") (pintype "passive"))
      (node (ref "GPS_C4") (pin "1") (pinfunction "1_1") (pintype "passive"))
      (node (ref "GPS_C5") (pin "1") (pinfunction "1_1") (pintype "passive"))
      (node (ref "IC1") (pin "7") (pinfunction "VSS_7") (pintype "power_in"))
      (node (ref "IC4") (pin "11") (pinfunction "GND_11") (pintype "power_in"))
      (node (ref "IC4") (pin "32") (pinfunction "GND1_32") (pintype "power_in"))
      (node (ref "IC4") (pin "51") (pinfunction "(WR)PG0_51") (pintype "bidirectional"))
      (node (ref "IC4") (pin "62") (pinfunction "GND2_62") (pintype "power_in"))
      (node (ref "IC4") (pin "81") (pinfunction "GND3_81") (pintype "power_in"))
      (node (ref "IC4") (pin "99") (pinfunction "AGND_99") (pintype "power_in"))
      (node (ref "JP1") (pin "1") (pinfunction "1_1") (pintype "passive"))
      (node (ref "JP2") (pin "1") (pinfunction "1_1") (pintype "passive"))
      (node (ref "NHD_2.7") (pin "GND0") (pinfunction "GND_GND0") (pintype "power_in"))
      (node (ref "NHD_2.7") (pin "GND1") (pinfunction "GND2_GND1") (pintype "power_in"))
      (node (ref "NHD_2.7") (pin "GND2") (pinfunction "GND3_GND2") (pintype "power_in"))
      (node (ref "NHD_2.7") (pin "GND3") (pinfunction "GND4_GND3") (pintype "power_in"))
      (node (ref "NHD_2.7") (pin "GND4") (pinfunction "GND5_GND4") (pintype "power_in"))
      (node (ref "NHD_2.7") (pin "GND5") (pinfunction "GND6_GND5") (pintype "power_in"))
      (node (ref "NHD_2.7") (pin "GND6") (pinfunction "GND7_GND6") (pintype "power_in"))
      (node (ref "NHD_2.7") (pin "GND7") (pinfunction "GND8_GND7") (pintype "power_in"))
      (node (ref "NHD_2.7") (pin "GND8") (pinfunction "GND9_GND8") (pintype "power_in"))
      (node (ref "NHD_2.7") (pin "GND9") (pinfunction "GND10_GND9") (pintype "power_in"))
      (node (ref "PE") (pin "1") (pinfunction "1_1") (pintype "passive"))
      (node (ref "PWR") (pin "3") (pinfunction "3_3") (pintype "passive"))
      (node (ref "PWR1") (pin "1") (pinfunction "1_1") (pintype "passive"))
      (node (ref "RX_L") (pin "1") (pinfunction "1_1") (pintype "passive"))
      (node (ref "R_BL_L1") (pin "2") (pinfunction "2_2") (pintype "passive"))
      (node (ref "R_B_LED_12") (pin "2") (pinfunction "2_2") (pintype "passive"))
      (node (ref "R_B_LED_13") (pin "2") (pinfunction "2_2") (pintype "passive"))
      (node (ref "R_B_LED_14") (pin "2") (pinfunction "2_2") (pintype "passive"))
      (node (ref "R_B_LED_15") (pin "2") (pinfunction "2_2") (pintype "passive"))
      (node (ref "R_B_LED_16") (pin "1") (pinfunction "1_1") (pintype "passive"))
      (node (ref "R_B_LED_17") (pin "1") (pinfunction "1_1") (pintype "passive"))
      (node (ref "R_B_LED_18") (pin "1") (pinfunction "1_1") (pintype "passive"))
      (node (ref "R_B_LED_19") (pin "1") (pinfunction "1_1") (pintype "passive"))
      (node (ref "R_B_LED_20") (pin "1") (pinfunction "1_1") (pintype "passive"))
      (node (ref "R_DEAKT_DAUER_P1") (pin "2") (pinfunction "2_2") (pintype "passive"))
      (node (ref "R_DZ_DOWN") (pin "2") (pinfunction "2_2") (pintype "passive"))
      (node (ref "R_E1_3") (pin "1") (pinfunction "1_1") (pintype "passive"))
      (node (ref "R_E2_2") (pin "2") (pinfunction "2_2") (pintype "passive"))
      (node (ref "R_FLASHL_DOWN") (pin "2") (pinfunction "2_2") (pintype "passive"))
      (node (ref "R_FLASHR_DOWN") (pin "2") (pinfunction "2_2") (pintype "passive"))
      (node (ref "R_HB_DOWN") (pin "2") (pinfunction "2_2") (pintype "passive"))
      (node (ref "R_REED_DOWN") (pin "2") (pinfunction "2_2") (pintype "passive"))
      (node (ref "R_R_LED_12") (pin "1") (pinfunction "1_1") (pintype "passive"))
      (node (ref "R_TX_DOWN") (pin "2") (pinfunction "2_2") (pintype "passive"))
      (node (ref "R_V_LOW") (pin "2") (pinfunction "2_2") (pintype "passive"))
      (node (ref "S1") (pin "1") (pinfunction "1_1") (pintype "passive"))
      (node (ref "SPEEDOSTECKER") (pin "P$11") (pinfunction "GND_P$11") (pintype "power_in"))
      (node (ref "ST2") (pin "6") (pinfunction "GND_6") (pintype "bidirectional"))
      (node (ref "ST2") (pin "GND") (pinfunction "SCHIRM1_GND") (pintype "bidirectional"))
      (node (ref "ST2") (pin "GND2") (pinfunction "SCHIRM2_GND2") (pintype "bidirectional"))
      (node (ref "ST2") (pin "GND3") (pinfunction "SCHIRM3_GND3") (pintype "bidirectional"))
      (node (ref "ST2") (pin "GND4") (pinfunction "SCHIRM_GND4") (pintype "bidirectional"))
      (node (ref "T1") (pin "2") (pinfunction "S_2") (pintype "passive"))
      (node (ref "T10") (pin "2") (pinfunction "S_2") (pintype "passive"))
      (node (ref "T11") (pin "2") (pinfunction "S_2") (pintype "passive"))
      (node (ref "T12") (pin "2") (pinfunction "S_2") (pintype "passive"))
      (node (ref "T13") (pin "2") (pinfunction "S_2") (pintype "passive"))
      (node (ref "T2") (pin "2") (pinfunction "S_2") (pintype "passive"))
      (node (ref "T3") (pin "2") (pinfunction "S_2") (pintype "passive"))
      (node (ref "T6") (pin "2") (pinfunction "S_2") (pintype "passive"))
      (node (ref "T7") (pin "2") (pinfunction "S_2") (pintype "passive"))
      (node (ref "T8") (pin "2") (pinfunction "S_2") (pintype "passive"))
      (node (ref "T9") (pin "2") (pinfunction "S_2") (pintype "passive"))
      (node (ref "TEMP_SENS") (pin "4") (pinfunction "GND_4") (pintype "power_in"))
      (node (ref "TEMP_SENS") (pin "5") (pinfunction "A2_5") (pintype "bidirectional"))
      (node (ref "TEMP_SENS") (pin "6") (pinfunction "A1_6") (pintype "bidirectional"))
      (node (ref "TEMP_SENS") (pin "7") (pinfunction "A0_7") (pintype "bidirectional"))
      (node (ref "U$1") (pin "21") (pinfunction "GND_21") (pintype "power_in"))
      (node (ref "U$1") (pin "3") (pinfunction "GND_3") (pintype "power_in"))
      (node (ref "U$1") (pin "5") (pinfunction "GND_5") (pintype "power_in"))
      (node (ref "U$14") (pin "10") (pinfunction "GND_10") (pintype "bidirectional"))
      (node (ref "U$14") (pin "19") (pinfunction "NOT(OE)_19") (pintype "bidirectional"))
      (node (ref "U$19") (pin "10") (pinfunction "GND_10") (pintype "bidirectional"))
      (node (ref "U$19") (pin "15") (pinfunction "ADR0_15") (pintype "bidirectional"))
      (node (ref "U$19") (pin "16") (pinfunction "ADR1_16") (pintype "bidirectional"))
      (node (ref "U$19") (pin "17") (pinfunction "ADR2_17") (pintype "bidirectional"))
    )
    (net (code "113") (name "Net-(5V_F-PadP$2)") (class "Default")
      (node (ref "5V_F") (pin "P$2") (pinfunction "P$2_P$2") (pintype "bidirectional"))
      (node (ref "5V_SUPPLY") (pin "OUT") (pinfunction "OUT_OUT") (pintype "bidirectional"))
      (node (ref "C18") (pin "1") (pinfunction "1_1") (pintype "passive"))
    )
    (net (code "114") (name "Net-(12V_F1-PadP$2)") (class "Default")
      (node (ref "12V_F1") (pin "P$2") (pinfunction "P$2_P$2") (pintype "bidirectional"))
      (node (ref "C39") (pin "1") (pinfunction "1_1") (pintype "passive"))
      (node (ref "L10") (pin "1") (pinfunction "1_1") (pintype "passive"))
    )
    (net (code "115") (name "Net-(BLUETOOTH-P$11PIO(5))") (class "Default")
      (node (ref "BLUETOOTH") (pin "P$11") (pinfunction "P$11PIO(5)_P$11") (pintype "bidirectional"))
      (node (ref "R_DATA") (pin "2") (pinfunction "2_2") (pintype "passive"))
    )
    (net (code "116") (name "Net-(CP1-PLUS)") (class "Default")
      (node (ref "CP1") (pin "POS") (pinfunction "PLUS_POS") (pintype "power_in"))
      (node (ref "CP2") (pin "POS") (pinfunction "PLUS_POS") (pintype "power_in"))
      (node (ref "D11") (pin "3") (pinfunction "C_3") (pintype "passive"))
      (node (ref "L10") (pin "2") (pinfunction "2_2") (pintype "passive"))
      (node (ref "L8") (pin "1") (pinfunction "1_1") (pintype "passive"))
    )
    (net (code "117") (name "Net-(D4-A)") (class "Default")
      (node (ref "D4") (pin "1") (pinfunction "A_1") (pintype "passive"))
      (node (ref "R_DATA") (pin "1") (pinfunction "1_1") (pintype "passive"))
    )
    (net (code "118") (name "Net-(D5-A)") (class "Default")
      (node (ref "D5") (pin "1") (pinfunction "A_1") (pintype "passive"))
      (node (ref "R_CNT") (pin "1") (pinfunction "1_1") (pintype "passive"))
    )
    (net (code "119") (name "Net-(D11-A)") (class "Default")
      (node (ref "D11") (pin "1") (pinfunction "A_1") (pintype "passive"))
      (node (ref "R_R_LED_12") (pin "2") (pinfunction "2_2") (pintype "passive"))
    )
    (net (code "120") (name "Net-(D12-A)") (class "Default")
      (node (ref "D12") (pin "1") (pinfunction "A_1") (pintype "passive"))
      (node (ref "IC4") (pin "67") (pinfunction "PJ4(PCINT13)_67") (pintype "bidirectional"))
    )
    (net (code "121") (name "Net-(D14-A)") (class "Default")
      (node (ref "D14") (pin "1") (pinfunction "A_1") (pintype "passive"))
      (node (ref "R_DEAKT_DAUER_P") (pin "2") (pinfunction "2_2") (pintype "passive"))
      (node (ref "R_DEAKT_DAUER_P2") (pin "1") (pinfunction "1_1") (pintype "passive"))
      (node (ref "T13") (pin "3") (pinfunction "D_3") (pintype "passive"))
    )
    (net (code "122") (name "Net-(D15-PadC)") (class "Default")
      (node (ref "D15") (pin "C") (pinfunction "C_C") (pintype "passive"))
      (node (ref "GPS") (pin "VBACKUP") (pinfunction "VBACKUP_VBACKUP") (pintype "bidirectional"))
      (node (ref "GPS_C2") (pin "1") (pinfunction "1_1") (pintype "passive"))
    )
    (net (code "123") (name "Net-(D18-C)") (class "Default")
      (node (ref "D18") (pin "3") (pinfunction "C_3") (pintype "passive"))
      (node (ref "R_E1_1") (pin "1") (pinfunction "1_1") (pintype "passive"))
      (node (ref "R_HB3") (pin "2") (pinfunction "2_2") (pintype "passive"))
    )
    (net (code "124") (name "Net-(D_GPS_FIX-A)") (class "Default")
      (node (ref "D_GPS_FIX") (pin "1") (pinfunction "A_1") (pintype "passive"))
      (node (ref "R_GPS_LED") (pin "2") (pinfunction "2_2") (pintype "passive"))
    )
    (net (code "125") (name "Net-(D_GR_BLR-CATHODE)") (class "Default")
      (node (ref "D_GR_BLR") (pin "P$4") (pinfunction "CATHODE_P$4") (pintype "bidirectional"))
      (node (ref "R_BL_R") (pin "1") (pinfunction "1_1") (pintype "passive"))
    )
    (net (code "126") (name "Net-(D_GR_N-CATHODE)") (class "Default")
      (node (ref "D_GR_N") (pin "P$4") (pinfunction "CATHODE_P$4") (pintype "bidirectional"))
      (node (ref "R_N") (pin "1") (pinfunction "1_1") (pintype "passive"))
    )
    (net (code "127") (name "Net-(D_L0-A)") (class "Default")
      (node (ref "D_L0") (pin "1") (pinfunction "A_1") (pintype "passive"))
      (node (ref "R_L0") (pin "2") (pinfunction "2_2") (pintype "passive"))
    )
    (net (code "128") (name "Net-(D_L1-A)") (class "Default")
      (node (ref "D_L1") (pin "1") (pinfunction "A_1") (pintype "passive"))
      (node (ref "R_L1") (pin "2") (pinfunction "2_2") (pintype "passive"))
    )
    (net (code "129") (name "Net-(D_L2-A)") (class "Default")
      (node (ref "D_L2") (pin "1") (pinfunction "A_1") (pintype "passive"))
      (node (ref "R_L2") (pin "2") (pinfunction "2_2") (pintype "passive"))
    )
    (net (code "130") (name "Net-(D_PWR_LED-A)") (class "Default")
      (node (ref "D_PWR_LED") (pin "1") (pinfunction "A_1") (pintype "passive"))
      (node (ref "R_LED_5V") (pin "2") (pinfunction "2_2") (pintype "passive"))
    )
    (net (code "131") (name "Net-(GPS_BAT-+)") (class "Default")
      (node (ref "D15") (pin "A") (pinfunction "A_A") (pintype "passive"))
      (node (ref "GPS_BAT") (pin "PWR@1") (pinfunction "+_PWR@1") (pintype "power_in"))
    )
    (net (code "132") (name "Net-(IC1C-I1)") (class "Default")
      (node (ref "IC1") (pin "9") (pinfunction "I1_9") (pintype "input"))
      (node (ref "R_E1_0") (pin "1") (pinfunction "1_1") (pintype "passive"))
      (node (ref "R_E1_1") (pin "2") (pinfunction "2_2") (pintype "passive"))
      (node (ref "R_E1_2") (pin "1") (pinfunction "1_1") (pintype "passive"))
      (node (ref "R_E1_3") (pin "2") (pinfunction "2_2") (pintype "passive"))
    )
    (net (code "133") (name "Net-(IC1C-O)") (class "Default")
      (node (ref "IC1") (pin "10") (pinfunction "O_10") (pintype "output"))
      (node (ref "R_E1_4") (pin "1") (pinfunction "1_1") (pintype "passive"))
    )
    (net (code "134") (name "Net-(IC1D-I0)") (class "Default")
      (node (ref "IC1") (pin "12") (pinfunction "I0_12") (pintype "input"))
      (node (ref "R_REED") (pin "2") (pinfunction "2_2") (pintype "passive"))
      (node (ref "R_REED_DOWN") (pin "1") (pinfunction "1_1") (pintype "passive"))
      (node (ref "R_REED_UP") (pin "2") (pinfunction "2_2") (pintype "passive"))
    )
    (net (code "135") (name "Net-(IC4-AREF)") (class "Default")
      (node (ref "C31") (pin "1") (pinfunction "1_1") (pintype "passive"))
      (node (ref "IC4") (pin "98") (pinfunction "AREF_98") (pintype "bidirectional"))
    )
    (net (code "136") (name "Net-(IC4-XTAL1)") (class "Default")
      (node (ref "16MHZ") (pin "1") (pinfunction "1_1") (pintype "passive"))
      (node (ref "C7") (pin "1") (pinfunction "1_1") (pintype "passive"))
      (node (ref "IC4") (pin "34") (pinfunction "XTAL1_34") (pintype "input"))
    )
    (net (code "137") (name "Net-(IC4-XTAL2)") (class "Default")
      (node (ref "16MHZ") (pin "2") (pinfunction "2_2") (pintype "passive"))
      (node (ref "C5") (pin "1") (pinfunction "1_1") (pintype "passive"))
      (node (ref "IC4") (pin "33") (pinfunction "XTAL2_33") (pintype "output"))
    )
    (net (code "138") (name "Net-(Q1-D)") (class "Default")
      (node (ref "Q1") (pin "3") (pinfunction "D_3") (pintype "passive"))
      (node (ref "RGB_7") (pin "1+") (pinfunction "R_+_1+") (pintype "bidirectional"))
      (node (ref "RGB_7") (pin "2+") (pinfunction "G_+_2+") (pintype "bidirectional"))
      (node (ref "RGB_7") (pin "3+") (pinfunction "B_+_3+") (pintype "bidirectional"))
    )
    (net (code "139") (name "Net-(Q1-G)") (class "Default")
      (node (ref "Q1") (pin "1") (pinfunction "G_1") (pintype "passive"))
      (node (ref "U$19") (pin "1") (pinfunction "B0_1") (pintype "bidirectional"))
    )
    (net (code "140") (name "Net-(Q2-D)") (class "Default")
      (node (ref "Q2") (pin "3") (pinfunction "D_3") (pintype "passive"))
      (node (ref "RGB_6") (pin "1+") (pinfunction "R_+_1+") (pintype "bidirectional"))
      (node (ref "RGB_6") (pin "2+") (pinfunction "G_+_2+") (pintype "bidirectional"))
      (node (ref "RGB_6") (pin "3+") (pinfunction "B_+_3+") (pintype "bidirectional"))
    )
    (net (code "141") (name "Net-(Q2-G)") (class "Default")
      (node (ref "Q2") (pin "1") (pinfunction "G_1") (pintype "passive"))
      (node (ref "U$19") (pin "2") (pinfunction "B1_2") (pintype "bidirectional"))
    )
    (net (code "142") (name "Net-(Q3-D)") (class "Default")
      (node (ref "Q3") (pin "3") (pinfunction "D_3") (pintype "passive"))
      (node (ref "RGB_5") (pin "1+") (pinfunction "R_+_1+") (pintype "bidirectional"))
      (node (ref "RGB_5") (pin "2+") (pinfunction "G_+_2+") (pintype "bidirectional"))
      (node (ref "RGB_5") (pin "3+") (pinfunction "B_+_3+") (pintype "bidirectional"))
    )
    (net (code "143") (name "Net-(Q3-G)") (class "Default")
      (node (ref "Q3") (pin "1") (pinfunction "G_1") (pintype "passive"))
      (node (ref "U$19") (pin "3") (pinfunction "B2_3") (pintype "bidirectional"))
    )
    (net (code "144") (name "Net-(Q4-D)") (class "Default")
      (node (ref "Q4") (pin "3") (pinfunction "D_3") (pintype "passive"))
      (node (ref "RGB_4") (pin "1+") (pinfunction "R_+_1+") (pintype "bidirectional"))
      (node (ref "RGB_4") (pin "2+") (pinfunction "G_+_2+") (pintype "bidirectional"))
      (node (ref "RGB_4") (pin "3+") (pinfunction "B_+_3+") (pintype "bidirectional"))
    )
    (net (code "145") (name "Net-(Q4-G)") (class "Default")
      (node (ref "Q4") (pin "1") (pinfunction "G_1") (pintype "passive"))
      (node (ref "U$19") (pin "4") (pinfunction "B3_4") (pintype "bidirectional"))
    )
    (net (code "146") (name "Net-(Q5-D)") (class "Default")
      (node (ref "Q5") (pin "3") (pinfunction "D_3") (pintype "passive"))
      (node (ref "RGB_3") (pin "1+") (pinfunction "R_+_1+") (pintype "bidirectional"))
      (node (ref "RGB_3") (pin "2+") (pinfunction "G_+_2+") (pintype "bidirectional"))
      (node (ref "RGB_3") (pin "3+") (pinfunction "B_+_3+") (pintype "bidirectional"))
    )
    (net (code "147") (name "Net-(Q5-G)") (class "Default")
      (node (ref "Q5") (pin "1") (pinfunction "G_1") (pintype "passive"))
      (node (ref "U$19") (pin "5") (pinfunction "B4_5") (pintype "bidirectional"))
    )
    (net (code "148") (name "Net-(Q6-D)") (class "Default")
      (node (ref "Q6") (pin "3") (pinfunction "D_3") (pintype "passive"))
      (node (ref "RGB_2") (pin "1+") (pinfunction "R_+_1+") (pintype "bidirectional"))
      (node (ref "RGB_2") (pin "2+") (pinfunction "G_+_2+") (pintype "bidirectional"))
      (node (ref "RGB_2") (pin "3+") (pinfunction "B_+_3+") (pintype "bidirectional"))
    )
    (net (code "149") (name "Net-(Q6-G)") (class "Default")
      (node (ref "Q6") (pin "1") (pinfunction "G_1") (pintype "passive"))
      (node (ref "U$19") (pin "6") (pinfunction "B5_6") (pintype "bidirectional"))
    )
    (net (code "150") (name "Net-(Q7-D)") (class "Default")
      (node (ref "Q7") (pin "3") (pinfunction "D_3") (pintype "passive"))
      (node (ref "RGB_9") (pin "1+") (pinfunction "R_+_1+") (pintype "bidirectional"))
      (node (ref "RGB_9") (pin "2+") (pinfunction "G_+_2+") (pintype "bidirectional"))
      (node (ref "RGB_9") (pin "3+") (pinfunction "B_+_3+") (pintype "bidirectional"))
    )
    (net (code "151") (name "Net-(Q7-G)") (class "Default")
      (node (ref "Q7") (pin "1") (pinfunction "G_1") (pintype "passive"))
      (node (ref "U$19") (pin "7") (pinfunction "B6_7") (pintype "bidirectional"))
    )
    (net (code "152") (name "Net-(Q8-D)") (class "Default")
      (node (ref "Q8") (pin "3") (pinfunction "D_3") (pintype "passive"))
      (node (ref "RGB_8") (pin "1+") (pinfunction "R_+_1+") (pintype "bidirectional"))
      (node (ref "RGB_8") (pin "2+") (pinfunction "G_+_2+") (pintype "bidirectional"))
      (node (ref "RGB_8") (pin "3+") (pinfunction "B_+_3+") (pintype "bidirectional"))
    )
    (net (code "153") (name "Net-(Q8-G)") (class "Default")
      (node (ref "Q8") (pin "1") (pinfunction "G_1") (pintype "passive"))
      (node (ref "U$19") (pin "8") (pinfunction "B7_8") (pintype "bidirectional"))
    )
    (net (code "154") (name "Net-(Q9-D)") (class "Default")
      (node (ref "Q9") (pin "3") (pinfunction "D_3") (pintype "passive"))
      (node (ref "RGB_1") (pin "1+") (pinfunction "R_+_1+") (pintype "bidirectional"))
      (node (ref "RGB_1") (pin "2+") (pinfunction "G_+_2+") (pintype "bidirectional"))
      (node (ref "RGB_1") (pin "3+") (pinfunction "B_+_3+") (pintype "bidirectional"))
    )
    (net (code "155") (name "Net-(Q9-G)") (class "Default")
      (node (ref "Q9") (pin "1") (pinfunction "G_1") (pintype "passive"))
      (node (ref "U$19") (pin "21") (pinfunction "A0_21") (pintype "bidirectional"))
    )
    (net (code "156") (name "Net-(Q10-D)") (class "Default")
      (node (ref "Q10") (pin "3") (pinfunction "D_3") (pintype "passive"))
      (node (ref "RGB_10") (pin "1+") (pinfunction "R_+_1+") (pintype "bidirectional"))
      (node (ref "RGB_10") (pin "2+") (pinfunction "G_+_2+") (pintype "bidirectional"))
      (node (ref "RGB_10") (pin "3+") (pinfunction "B_+_3+") (pintype "bidirectional"))
    )
    (net (code "157") (name "Net-(Q10-G)") (class "Default")
      (node (ref "Q10") (pin "1") (pinfunction "G_1") (pintype "passive"))
      (node (ref "U$19") (pin "22") (pinfunction "A1_22") (pintype "bidirectional"))
    )
    (net (code "158") (name "Net-(Q11-D)") (class "Default")
      (node (ref "Q11") (pin "3") (pinfunction "D_3") (pintype "passive"))
      (node (ref "RGB_11") (pin "1+") (pinfunction "R_+_1+") (pintype "bidirectional"))
      (node (ref "RGB_11") (pin "2+") (pinfunction "G_+_2+") (pintype "bidirectional"))
      (node (ref "RGB_11") (pin "3+") (pinfunction "B_+_3+") (pintype "bidirectional"))
    )
    (net (code "159") (name "Net-(Q11-G)") (class "Default")
      (node (ref "Q11") (pin "1") (pinfunction "G_1") (pintype "passive"))
      (node (ref "U$19") (pin "23") (pinfunction "A2_23") (pintype "bidirectional"))
    )
    (net (code "160") (name "Net-(RGB_1-B_-)") (class "Default")
      (node (ref "RGB_1") (pin "3-") (pinfunction "B_-_3-") (pintype "bidirectional"))
      (node (ref "R_B_LED_11") (pin "1") (pinfunction "1_1") (pintype "passive"))
    )
    (net (code "161") (name "Net-(RGB_1-G_-)") (class "Default")
      (node (ref "RGB_1") (pin "2-") (pinfunction "G_-_2-") (pintype "bidirectional"))
      (node (ref "R_G_LED_11") (pin "1") (pinfunction "1_1") (pintype "passive"))
    )
    (net (code "162") (name "Net-(RGB_1-R_-)") (class "Default")
      (node (ref "RGB_1") (pin "1-") (pinfunction "R_-_1-") (pintype "bidirectional"))
      (node (ref "R_R_LED_11") (pin "1") (pinfunction "1_1") (pintype "passive"))
    )
    (net (code "163") (name "Net-(RGB_2-B_-)") (class "Default")
      (node (ref "RGB_2") (pin "3-") (pinfunction "B_-_3-") (pintype "bidirectional"))
      (node (ref "R_B_LED_1") (pin "1") (pinfunction "1_1") (pintype "passive"))
    )
    (net (code "164") (name "Net-(RGB_2-G_-)") (class "Default")
      (node (ref "RGB_2") (pin "2-") (pinfunction "G_-_2-") (pintype "bidirectional"))
      (node (ref "R_G_LED_1") (pin "1") (pinfunction "1_1") (pintype "passive"))
    )
    (net (code "165") (name "Net-(RGB_2-R_-)") (class "Default")
      (node (ref "RGB_2") (pin "1-") (pinfunction "R_-_1-") (pintype "bidirectional"))
      (node (ref "R_R_LED_1") (pin "1") (pinfunction "1_1") (pintype "passive"))
    )
    (net (code "166") (name "Net-(RGB_3-B_-)") (class "Default")
      (node (ref "RGB_3") (pin "3-") (pinfunction "B_-_3-") (pintype "bidirectional"))
      (node (ref "R_B_LED_2") (pin "1") (pinfunction "1_1") (pintype "passive"))
    )
    (net (code "167") (name "Net-(RGB_3-G_-)") (class "Default")
      (node (ref "RGB_3") (pin "2-") (pinfunction "G_-_2-") (pintype "bidirectional"))
      (node (ref "R_G_LED_2") (pin "1") (pinfunction "1_1") (pintype "passive"))
    )
    (net (code "168") (name "Net-(RGB_3-R_-)") (class "Default")
      (node (ref "RGB_3") (pin "1-") (pinfunction "R_-_1-") (pintype "bidirectional"))
      (node (ref "R_R_LED_2") (pin "1") (pinfunction "1_1") (pintype "passive"))
    )
    (net (code "169") (name "Net-(RGB_4-B_-)") (class "Default")
      (node (ref "RGB_4") (pin "3-") (pinfunction "B_-_3-") (pintype "bidirectional"))
      (node (ref "R_B_LED_3") (pin "1") (pinfunction "1_1") (pintype "passive"))
    )
    (net (code "170") (name "Net-(RGB_4-G_-)") (class "Default")
      (node (ref "RGB_4") (pin "2-") (pinfunction "G_-_2-") (pintype "bidirectional"))
      (node (ref "R_G_LED_3") (pin "1") (pinfunction "1_1") (pintype "passive"))
    )
    (net (code "171") (name "Net-(RGB_4-R_-)") (class "Default")
      (node (ref "RGB_4") (pin "1-") (pinfunction "R_-_1-") (pintype "bidirectional"))
      (node (ref "R_R_LED_3") (pin "1") (pinfunction "1_1") (pintype "passive"))
    )
    (net (code "172") (name "Net-(RGB_5-B_-)") (class "Default")
      (node (ref "RGB_5") (pin "3-") (pinfunction "B_-_3-") (pintype "bidirectional"))
      (node (ref "R_B_LED_4") (pin "1") (pinfunction "1_1") (pintype "passive"))
    )
    (net (code "173") (name "Net-(RGB_5-G_-)") (class "Default")
      (node (ref "RGB_5") (pin "2-") (pinfunction "G_-_2-") (pintype "bidirectional"))
      (node (ref "R_G_LED_4") (pin "1") (pinfunction "1_1") (pintype "passive"))
    )
    (net (code "174") (name "Net-(RGB_5-R_-)") (class "Default")
      (node (ref "RGB_5") (pin "1-") (pinfunction "R_-_1-") (pintype "bidirectional"))
      (node (ref "R_R_LED_4") (pin "1") (pinfunction "1_1") (pintype "passive"))
    )
    (net (code "175") (name "Net-(RGB_6-B_-)") (class "Default")
      (node (ref "RGB_6") (pin "3-") (pinfunction "B_-_3-") (pintype "bidirectional"))
      (node (ref "R_B_LED_5") (pin "1") (pinfunction "1_1") (pintype "passive"))
    )
    (net (code "176") (name "Net-(RGB_6-G_-)") (class "Default")
      (node (ref "RGB_6") (pin "2-") (pinfunction "G_-_2-") (pintype "bidirectional"))
      (node (ref "R_G_LED_5") (pin "1") (pinfunction "1_1") (pintype "passive"))
    )
    (net (code "177") (name "Net-(RGB_6-R_-)") (class "Default")
      (node (ref "RGB_6") (pin "1-") (pinfunction "R_-_1-") (pintype "bidirectional"))
      (node (ref "R_R_LED_5") (pin "1") (pinfunction "1_1") (pintype "passive"))
    )
    (net (code "178") (name "Net-(RGB_7-B_-)") (class "Default")
      (node (ref "RGB_7") (pin "3-") (pinfunction "B_-_3-") (pintype "bidirectional"))
      (node (ref "R_B_LED_6") (pin "1") (pinfunction "1_1") (pintype "passive"))
    )
    (net (code "179") (name "Net-(RGB_7-G_-)") (class "Default")
      (node (ref "RGB_7") (pin "2-") (pinfunction "G_-_2-") (pintype "bidirectional"))
      (node (ref "R_G_LED_6") (pin "1") (pinfunction "1_1") (pintype "passive"))
    )
    (net (code "180") (name "Net-(RGB_7-R_-)") (class "Default")
      (node (ref "RGB_7") (pin "1-") (pinfunction "R_-_1-") (pintype "bidirectional"))
      (node (ref "R_R_LED_6") (pin "1") (pinfunction "1_1") (pintype "passive"))
    )
    (net (code "181") (name "Net-(RGB_8-B_-)") (class "Default")
      (node (ref "RGB_8") (pin "3-") (pinfunction "B_-_3-") (pintype "bidirectional"))
      (node (ref "R_B_LED_10") (pin "1") (pinfunction "1_1") (pintype "passive"))
    )
    (net (code "182") (name "Net-(RGB_8-G_-)") (class "Default")
      (node (ref "RGB_8") (pin "2-") (pinfunction "G_-_2-") (pintype "bidirectional"))
      (node (ref "R_G_LED_10") (pin "1") (pinfunction "1_1") (pintype "passive"))
    )
    (net (code "183") (name "Net-(RGB_8-R_-)") (class "Default")
      (node (ref "RGB_8") (pin "1-") (pinfunction "R_-_1-") (pintype "bidirectional"))
      (node (ref "R_R_LED_10") (pin "1") (pinfunction "1_1") (pintype "passive"))
    )
    (net (code "184") (name "Net-(RGB_9-B_-)") (class "Default")
      (node (ref "RGB_9") (pin "3-") (pinfunction "B_-_3-") (pintype "bidirectional"))
      (node (ref "R_B_LED_9") (pin "1") (pinfunction "1_1") (pintype "passive"))
    )
    (net (code "185") (name "Net-(RGB_9-G_-)") (class "Default")
      (node (ref "RGB_9") (pin "2-") (pinfunction "G_-_2-") (pintype "bidirectional"))
      (node (ref "R_G_LED_9") (pin "1") (pinfunction "1_1") (pintype "passive"))
    )
    (net (code "186") (name "Net-(RGB_9-R_-)") (class "Default")
      (node (ref "RGB_9") (pin "1-") (pinfunction "R_-_1-") (pintype "bidirectional"))
      (node (ref "R_R_LED_9") (pin "1") (pinfunction "1_1") (pintype "passive"))
    )
    (net (code "187") (name "Net-(RGB_10-B_-)") (class "Default")
      (node (ref "RGB_10") (pin "3-") (pinfunction "B_-_3-") (pintype "bidirectional"))
      (node (ref "R_B_LED_8") (pin "1") (pinfunction "1_1") (pintype "passive"))
    )
    (net (code "188") (name "Net-(RGB_10-G_-)") (class "Default")
      (node (ref "RGB_10") (pin "2-") (pinfunction "G_-_2-") (pintype "bidirectional"))
      (node (ref "R_G_LED_8") (pin "1") (pinfunction "1_1") (pintype "passive"))
    )
    (net (code "189") (name "Net-(RGB_10-R_-)") (class "Default")
      (node (ref "RGB_10") (pin "1-") (pinfunction "R_-_1-") (pintype "bidirectional"))
      (node (ref "R_R_LED_8") (pin "1") (pinfunction "1_1") (pintype "passive"))
    )
    (net (code "190") (name "Net-(RGB_11-B_-)") (class "Default")
      (node (ref "RGB_11") (pin "3-") (pinfunction "B_-_3-") (pintype "bidirectional"))
      (node (ref "R_B_LED_7") (pin "1") (pinfunction "1_1") (pintype "passive"))
    )
    (net (code "191") (name "Net-(RGB_11-G_-)") (class "Default")
      (node (ref "RGB_11") (pin "2-") (pinfunction "G_-_2-") (pintype "bidirectional"))
      (node (ref "R_G_LED_7") (pin "1") (pinfunction "1_1") (pintype "passive"))
    )
    (net (code "192") (name "Net-(RGB_11-R_-)") (class "Default")
      (node (ref "RGB_11") (pin "1-") (pinfunction "R_-_1-") (pintype "bidirectional"))
      (node (ref "R_R_LED_7") (pin "1") (pinfunction "1_1") (pintype "passive"))
    )
    (net (code "193") (name "Net-(R_GR_BL_L-CATHODE)") (class "Default")
      (node (ref "R_BL_L") (pin "1") (pinfunction "1_1") (pintype "passive"))
      (node (ref "R_GR_BL_L") (pin "P$4") (pinfunction "CATHODE_P$4") (pintype "bidirectional"))
    )
    (net (code "194") (name "Net-(SPEEDOSTECKER-DAUER_VIN)") (class "Default")
      (node (ref "R_DEAKT_DAUER_P") (pin "1") (pinfunction "1_1") (pintype "passive"))
      (node (ref "SPEEDOSTECKER") (pin "P$14") (pinfunction "DAUER_VIN_P$14") (pintype "bidirectional"))
      (node (ref "T_P_BRIDGE") (pin "2") (pinfunction "S_2") (pintype "passive"))
    )
    (net (code "195") (name "Net-(SPEEDOSTECKER-EX_IN_OUT_A2)") (class "Default")
      (node (ref "R_E2_1") (pin "1") (pinfunction "1_1") (pintype "passive"))
      (node (ref "SPEEDOSTECKER") (pin "P$16") (pinfunction "EX_IN_OUT_A2_P$16") (pintype "bidirectional"))
    )
    (net (code "196") (name "Net-(SPEEDOSTECKER-EX_IN_OUT_D1)") (class "Default")
      (node (ref "R_HB3") (pin "1") (pinfunction "1_1") (pintype "passive"))
      (node (ref "SPEEDOSTECKER") (pin "P$13") (pinfunction "EX_IN_OUT_D1_P$13") (pintype "bidirectional"))
    )
    (net (code "197") (name "Net-(SPEEDOSTECKER-MC_COI)") (class "Default")
      (node (ref "R_HB4") (pin "1") (pinfunction "1_1") (pintype "passive"))
      (node (ref "SPEEDOSTECKER") (pin "P$7") (pinfunction "MC_COI_P$7") (pintype "output"))
    )
    (net (code "198") (name "Net-(SPEEDOSTECKER-OIL_TEMP)") (class "Default")
      (node (ref "R_OIL_OV") (pin "1") (pinfunction "1_1") (pintype "passive"))
      (node (ref "R_OIL_UP") (pin "1") (pinfunction "1_1") (pintype "passive"))
      (node (ref "SPEEDOSTECKER") (pin "P$2") (pinfunction "OIL_TEMP_P$2") (pintype "input"))
    )
    (net (code "199") (name "Net-(SPEEDOSTECKER-WATER_TEMP)") (class "Default")
      (node (ref "R_OIL_OV1") (pin "1") (pinfunction "1_1") (pintype "passive"))
      (node (ref "R_WATER_UP") (pin "2") (pinfunction "2_2") (pintype "passive"))
      (node (ref "SPEEDOSTECKER") (pin "P$12") (pinfunction "WATER_TEMP_P$12") (pintype "input"))
    )
    (net (code "200") (name "Net-(T1-D)") (class "Default")
      (node (ref "R_B_LED_1") (pin "2") (pinfunction "2_2") (pintype "passive"))
      (node (ref "R_B_LED_10") (pin "2") (pinfunction "2_2") (pintype "passive"))
      (node (ref "R_B_LED_11") (pin "2") (pinfunction "2_2") (pintype "passive"))
      (node (ref "R_B_LED_2") (pin "2") (pinfunction "2_2") (pintype "passive"))
      (node (ref "R_B_LED_3") (pin "2") (pinfunction "2_2") (pintype "passive"))
      (node (ref "R_B_LED_4") (pin "2") (pinfunction "2_2") (pintype "passive"))
      (node (ref "R_B_LED_5") (pin "2") (pinfunction "2_2") (pintype "passive"))
      (node (ref "R_B_LED_6") (pin "2") (pinfunction "2_2") (pintype "passive"))
      (node (ref "R_B_LED_7") (pin "2") (pinfunction "2_2") (pintype "passive"))
      (node (ref "R_B_LED_8") (pin "2") (pinfunction "2_2") (pintype "passive"))
      (node (ref "R_B_LED_9") (pin "2") (pinfunction "2_2") (pintype "passive"))
      (node (ref "T1") (pin "3") (pinfunction "D_3") (pintype "passive"))
    )
    (net (code "201") (name "Net-(T2-D)") (class "Default")
      (node (ref "R_G_LED_1") (pin "2") (pinfunction "2_2") (pintype "passive"))
      (node (ref "R_G_LED_10") (pin "2") (pinfunction "2_2") (pintype "passive"))
      (node (ref "R_G_LED_11") (pin "2") (pinfunction "2_2") (pintype "passive"))
      (node (ref "R_G_LED_2") (pin "2") (pinfunction "2_2") (pintype "passive"))
      (node (ref "R_G_LED_3") (pin "2") (pinfunction "2_2") (pintype "passive"))
      (node (ref "R_G_LED_4") (pin "2") (pinfunction "2_2") (pintype "passive"))
      (node (ref "R_G_LED_5") (pin "2") (pinfunction "2_2") (pintype "passive"))
      (node (ref "R_G_LED_6") (pin "2") (pinfunction "2_2") (pintype "passive"))
      (node (ref "R_G_LED_7") (pin "2") (pinfunction "2_2") (pintype "passive"))
      (node (ref "R_G_LED_8") (pin "2") (pinfunction "2_2") (pintype "passive"))
      (node (ref "R_G_LED_9") (pin "2") (pinfunction "2_2") (pintype "passive"))
      (node (ref "T2") (pin "3") (pinfunction "D_3") (pintype "passive"))
    )
    (net (code "202") (name "Net-(T5-D)") (class "Default")
      (node (ref "R_GPS_LED") (pin "1") (pinfunction "1_1") (pintype "passive"))
      (node (ref "T5") (pin "3") (pinfunction "D_3") (pintype "bidirectional"))
    )
    (net (code "203") (name "Net-(T5-G)") (class "Default")
      (node (ref "GPS") (pin "3D-FIX") (pinfunction "3D-FIX_3D-FIX") (pintype "bidirectional"))
      (node (ref "T5") (pin "1") (pinfunction "G_1") (pintype "input"))
    )
    (net (code "204") (name "Net-(T6-D)") (class "Default")
      (node (ref "R_N") (pin "2") (pinfunction "2_2") (pintype "passive"))
      (node (ref "T6") (pin "3") (pinfunction "D_3") (pintype "passive"))
    )
    (net (code "205") (name "Net-(T7-D)") (class "Default")
      (node (ref "R_HIGHB") (pin "2") (pinfunction "2_2") (pintype "passive"))
      (node (ref "T7") (pin "3") (pinfunction "D_3") (pintype "passive"))
    )
    (net (code "206") (name "Net-(T8-D)") (class "Default")
      (node (ref "R_OIL") (pin "2") (pinfunction "2_2") (pintype "passive"))
      (node (ref "T8") (pin "3") (pinfunction "D_3") (pintype "passive"))
    )
    (net (code "207") (name "Net-(T9-D)") (class "Default")
      (node (ref "R_BL_R") (pin "2") (pinfunction "2_2") (pintype "passive"))
      (node (ref "T9") (pin "3") (pinfunction "D_3") (pintype "passive"))
    )
    (net (code "208") (name "Net-(T10-D)") (class "Default")
      (node (ref "R_BL_L") (pin "2") (pinfunction "2_2") (pintype "passive"))
      (node (ref "T10") (pin "3") (pinfunction "D_3") (pintype "passive"))
    )
    (net (code "209") (name "Net-(T11-D)") (class "Default")
      (node (ref "R_R_LED_0") (pin "2") (pinfunction "2_2") (pintype "passive"))
      (node (ref "T11") (pin "3") (pinfunction "D_3") (pintype "passive"))
    )
    (net (code "210") (name "Net-(T12-D)") (class "Default")
      (node (ref "R_R_LED_1") (pin "2") (pinfunction "2_2") (pintype "passive"))
      (node (ref "R_R_LED_10") (pin "2") (pinfunction "2_2") (pintype "passive"))
      (node (ref "R_R_LED_11") (pin "2") (pinfunction "2_2") (pintype "passive"))
      (node (ref "R_R_LED_2") (pin "2") (pinfunction "2_2") (pintype "passive"))
      (node (ref "R_R_LED_3") (pin "2") (pinfunction "2_2") (pintype "passive"))
      (node (ref "R_R_LED_4") (pin "2") (pinfunction "2_2") (pintype "passive"))
      (node (ref "R_R_LED_5") (pin "2") (pinfunction "2_2") (pintype "passive"))
      (node (ref "R_R_LED_6") (pin "2") (pinfunction "2_2") (pintype "passive"))
      (node (ref "R_R_LED_7") (pin "2") (pinfunction "2_2") (pintype "passive"))
      (node (ref "R_R_LED_8") (pin "2") (pinfunction "2_2") (pintype "passive"))
      (node (ref "R_R_LED_9") (pin "2") (pinfunction "2_2") (pintype "passive"))
      (node (ref "T12") (pin "3") (pinfunction "D_3") (pintype "passive"))
      (node (ref "T3") (pin "3") (pinfunction "D_3") (pintype "passive"))
    )
    (net (code "211") (name "Net-(TEMP_SENS-OS)") (class "Default")
      (node (ref "R_TEMP_OS") (pin "1") (pinfunction "1_1") (pintype "passive"))
      (node (ref "TEMP_SENS") (pin "3") (pinfunction "OS_3") (pintype "bidirectional"))
    )
    (net (code "212") (name "Net-(TEMP_SENS-VDD)") (class "Default")
      (node (ref "C6") (pin "1") (pinfunction "1_1") (pintype "passive"))
      (node (ref "R_DELAY") (pin "1") (pinfunction "1_1") (pintype "passive"))
      (node (ref "TEMP_SENS") (pin "8") (pinfunction "VDD_8") (pintype "power_in"))
    )
    (net (code "213") (name "Net-(T_P_BRIDGE-D)") (class "Default")
      (node (ref "D_VERPOL1") (pin "A") (pinfunction "A_A") (pintype "passive"))
      (node (ref "T_P_BRIDGE") (pin "3") (pinfunction "D_3") (pintype "passive"))
    )
    (net (code "214") (name "Net-(T_P_BRIDGE-G)") (class "Default")
      (node (ref "R_DEAKT_DAUER_P2") (pin "2") (pinfunction "2_2") (pintype "passive"))
      (node (ref "T_P_BRIDGE") (pin "1") (pinfunction "G_1") (pintype "passive"))
    )
    (net (code "215") (name "Net-(U$1-(PCINT6{slash}XTAL1{slash}TOSC1)PB6)") (class "Default")
      (node (ref "16MHZ1") (pin "1") (pinfunction "1_1") (pintype "passive"))
      (node (ref "C_QUA_5") (pin "2") (pinfunction "2_2") (pintype "passive"))
      (node (ref "U$1") (pin "7") (pinfunction "(PCINT6/XTAL1/TOSC1)PB6_7") (pintype "bidirectional"))
    )
    (net (code "216") (name "Net-(U$1-(PCINT7{slash}XTAL2{slash}TOSC2)PB7)") (class "Default")
      (node (ref "16MHZ1") (pin "2") (pinfunction "2_2") (pintype "passive"))
      (node (ref "C_QUA_4") (pin "2") (pinfunction "2_2") (pintype "passive"))
      (node (ref "U$1") (pin "8") (pinfunction "(PCINT7/XTAL2/TOSC2)PB7_8") (pintype "bidirectional"))
    )
    (net (code "217") (name "Net-(U$1-(PCINT21{slash}OC0B{slash}T1)PD5)") (class "Default")
      (node (ref "R_L0") (pin "1") (pinfunction "1_1") (pintype "passive"))
      (node (ref "U$1") (pin "9") (pinfunction "(PCINT21/OC0B/T1)PD5_9") (pintype "bidirectional"))
    )
    (net (code "218") (name "Net-(U$1-(PCINT22{slash}OC0A{slash}AIN0)PD6)") (class "Default")
      (node (ref "R_L1") (pin "1") (pinfunction "1_1") (pintype "passive"))
      (node (ref "U$1") (pin "10") (pinfunction "(PCINT22/OC0A/AIN0)PD6_10") (pintype "bidirectional"))
    )
    (net (code "219") (name "Net-(U$1-(PCINT23{slash}AIN1)PD7)") (class "Default")
      (node (ref "R_L2") (pin "1") (pinfunction "1_1") (pintype "passive"))
      (node (ref "U$1") (pin "11") (pinfunction "(PCINT23/AIN1)PD7_11") (pintype "bidirectional"))
    )
    (net (code "220") (name "Net-(U$1-AREF)") (class "Default")
      (node (ref "AT8_REF") (pin "2") (pinfunction "2_2") (pintype "passive"))
      (node (ref "C1") (pin "1") (pinfunction "1_1") (pintype "passive"))
      (node (ref "U$1") (pin "18") (pinfunction "AVCC_18") (pintype "power_in"))
      (node (ref "U$1") (pin "20") (pinfunction "AREF_20") (pintype "passive"))
    )
    (net (code "221") (name "Net-(U$3-CATHODE)") (class "Default")
      (node (ref "R_HIGHB") (pin "1") (pinfunction "1_1") (pintype "passive"))
      (node (ref "U$3") (pin "P$4") (pinfunction "CATHODE_P$4") (pintype "bidirectional"))
    )
    (net (code "222") (name "Net-(U$11-CATHODE)") (class "Default")
      (node (ref "R_OIL") (pin "1") (pinfunction "1_1") (pintype "passive"))
      (node (ref "U$11") (pin "P$4") (pinfunction "CATHODE_P$4") (pintype "bidirectional"))
    )
    (net (code "223") (name "Net-(U$22-CATHODE)") (class "Default")
      (node (ref "R_R_LED_0") (pin "1") (pinfunction "1_1") (pintype "passive"))
      (node (ref "U$22") (pin "P$4") (pinfunction "CATHODE_P$4") (pintype "bidirectional"))
    )
    (net (code "224") (name "VDD") (class "Default")
      (node (ref "5V_F") (pin "P$1") (pinfunction "P$1_P$1") (pintype "bidirectional"))
      (node (ref "C32") (pin "1") (pinfunction "1_1") (pintype "passive"))
      (node (ref "C33") (pin "1") (pinfunction "1_1") (pintype "passive"))
      (node (ref "C34") (pin "1") (pinfunction "1_1") (pintype "passive"))
      (node (ref "D9") (pin "A") (pinfunction "A_A") (pintype "passive"))
      (node (ref "D_GR_BLR") (pin "P$1") (pinfunction "ANODE_P$1") (pintype "bidirectional"))
      (node (ref "D_GR_BLR") (pin "P$2") (pinfunction "ANODE_P$2") (pintype "bidirectional"))
      (node (ref "D_GR_BLR") (pin "P$3") (pinfunction "ANODE_P$3") (pintype "bidirectional"))
      (node (ref "D_GR_N") (pin "P$1") (pinfunction "ANODE_P$1") (pintype "bidirectional"))
      (node (ref "D_GR_N") (pin "P$2") (pinfunction "ANODE_P$2") (pintype "bidirectional"))
      (node (ref "D_GR_N") (pin "P$3") (pinfunction "ANODE_P$3") (pintype "bidirectional"))
      (node (ref "IC1") (pin "1") (pinfunction "I0_1") (pintype "input"))
      (node (ref "IC1") (pin "13") (pinfunction "I1_13") (pintype "input"))
      (node (ref "IC1") (pin "14") (pinfunction "VDD_14") (pintype "power_in"))
      (node (ref "IC1") (pin "8") (pinfunction "I0_8") (pintype "input"))
      (node (ref "IC4") (pin "10") (pinfunction "VCC_10") (pintype "power_in"))
      (node (ref "IC4") (pin "100") (pinfunction "AVCC_100") (pintype "power_in"))
      (node (ref "IC4") (pin "31") (pinfunction "VCC1_31") (pintype "power_in"))
      (node (ref "IC4") (pin "61") (pinfunction "VCC2_61") (pintype "power_in"))
      (node (ref "IC4") (pin "80") (pinfunction "VCC3_80") (pintype "power_in"))
      (node (ref "JP1") (pin "5") (pinfunction "5_5") (pintype "passive"))
      (node (ref "PE") (pin "2") (pinfunction "2_2") (pintype "passive"))
      (node (ref "PWR") (pin "2") (pinfunction "2_2") (pintype "passive"))
      (node (ref "PWR1") (pin "2") (pinfunction "2_2") (pintype "passive"))
      (node (ref "Q1") (pin "2") (pinfunction "S_2") (pintype "passive"))
      (node (ref "Q10") (pin "2") (pinfunction "S_2") (pintype "passive"))
      (node (ref "Q11") (pin "2") (pinfunction "S_2") (pintype "passive"))
      (node (ref "Q2") (pin "2") (pinfunction "S_2") (pintype "passive"))
      (node (ref "Q3") (pin "2") (pinfunction "S_2") (pintype "passive"))
      (node (ref "Q4") (pin "2") (pinfunction "S_2") (pintype "passive"))
      (node (ref "Q5") (pin "2") (pinfunction "S_2") (pintype "passive"))
      (node (ref "Q6") (pin "2") (pinfunction "S_2") (pintype "passive"))
      (node (ref "Q7") (pin "2") (pinfunction "S_2") (pintype "passive"))
      (node (ref "Q8") (pin "2") (pinfunction "S_2") (pintype "passive"))
      (node (ref "Q9") (pin "2") (pinfunction "S_2") (pintype "passive"))
      (node (ref "R_DELAY") (pin "2") (pinfunction "2_2") (pintype "passive"))
      (node (ref "R_E1_0") (pin "2") (pinfunction "2_2") (pintype "passive"))
      (node (ref "R_GR_BL_L") (pin "P$1") (pinfunction "ANODE_P$1") (pintype "bidirectional"))
      (node (ref "R_GR_BL_L") (pin "P$2") (pinfunction "ANODE_P$2") (pintype "bidirectional"))
      (node (ref "R_GR_BL_L") (pin "P$3") (pinfunction "ANODE_P$3") (pintype "bidirectional"))
      (node (ref "R_L3") (pin "1") (pinfunction "1_1") (pintype "passive"))
      (node (ref "R_LED_5V") (pin "1") (pinfunction "1_1") (pintype "passive"))
      (node (ref "R_OIL_UP") (pin "2") (pinfunction "2_2") (pintype "passive"))
      (node (ref "R_REED_UP") (pin "1") (pinfunction "1_1") (pintype "passive"))
      (node (ref "R_RES_UP") (pin "2") (pinfunction "2_2") (pintype "passive"))
      (node (ref "R_SCL_UP") (pin "1") (pinfunction "1_1") (pintype "passive"))
      (node (ref "R_SDA_UP") (pin "1") (pinfunction "1_1") (pintype "passive"))
      (node (ref "R_TEMP_OS") (pin "2") (pinfunction "2_2") (pintype "passive"))
      (node (ref "R_WATER_UP") (pin "1") (pinfunction "1_1") (pintype "passive"))
      (node (ref "U$11") (pin "P$1") (pinfunction "ANODE_P$1") (pintype "bidirectional"))
      (node (ref "U$11") (pin "P$2") (pinfunction "ANODE_P$2") (pintype "bidirectional"))
      (node (ref "U$11") (pin "P$3") (pinfunction "ANODE_P$3") (pintype "bidirectional"))
      (node (ref "U$19") (pin "18") (pinfunction "NOT(RESET)_18") (pintype "bidirectional"))
      (node (ref "U$19") (pin "9") (pinfunction "VCC_9") (pintype "bidirectional"))
      (node (ref "U$22") (pin "P$1") (pinfunction "ANODE_P$1") (pintype "bidirectional"))
      (node (ref "U$22") (pin "P$2") (pinfunction "ANODE_P$2") (pintype "bidirectional"))
      (node (ref "U$22") (pin "P$3") (pinfunction "ANODE_P$3") (pintype "bidirectional"))
      (node (ref "U$3") (pin "P$1") (pinfunction "ANODE_P$1") (pintype "bidirectional"))
      (node (ref "U$3") (pin "P$2") (pinfunction "ANODE_P$2") (pintype "bidirectional"))
      (node (ref "U$3") (pin "P$3") (pinfunction "ANODE_P$3") (pintype "bidirectional"))
    )
    (net (code "225") (name "unconnected-(BLUETOOTH-P$3_AIO(0)-PadP$3)") (class "Default")
      (node (ref "BLUETOOTH") (pin "P$3") (pinfunction "P$3_AIO(0)_P$3") (pintype "bidirectional"))
    )
    (net (code "226") (name "unconnected-(BLUETOOTH-P$4_AIO(1)-PadP$4)") (class "Default")
      (node (ref "BLUETOOTH") (pin "P$4") (pinfunction "P$4_AIO(1)_P$4") (pintype "bidirectional"))
    )
    (net (code "227") (name "unconnected-(BLUETOOTH-P$5_PIO(0)-PadP$5)") (class "Default")
      (node (ref "BLUETOOTH") (pin "P$5") (pinfunction "P$5_PIO(0)_P$5") (pintype "bidirectional"))
    )
    (net (code "228") (name "unconnected-(BLUETOOTH-P$6_PIO(1)-PadP$6)") (class "Default")
      (node (ref "BLUETOOTH") (pin "P$6") (pinfunction "P$6_PIO(1)_P$6") (pintype "bidirectional"))
    )
    (net (code "229") (name "unconnected-(BLUETOOTH-P$7_PIO(2)-PadP$7)") (class "Default")
      (node (ref "BLUETOOTH") (pin "P$7") (pinfunction "P$7_PIO(2)_P$7") (pintype "bidirectional"))
    )
    (net (code "230") (name "unconnected-(BLUETOOTH-P$8_PIO(3)-PadP$8)") (class "Default")
      (node (ref "BLUETOOTH") (pin "P$8") (pinfunction "P$8_PIO(3)_P$8") (pintype "bidirectional"))
    )
    (net (code "231") (name "unconnected-(BLUETOOTH-P$9_PIO(4)-PadP$9)") (class "Default")
      (node (ref "BLUETOOTH") (pin "P$9") (pinfunction "P$9_PIO(4)_P$9") (pintype "bidirectional"))
    )
    (net (code "232") (name "unconnected-(BLUETOOTH-P$12_PIO(6)-PadP$12)") (class "Default")
      (node (ref "BLUETOOTH") (pin "P$12") (pinfunction "P$12_PIO(6)_P$12") (pintype "bidirectional"))
    )
    (net (code "233") (name "unconnected-(BLUETOOTH-P$14_PIO(8)-PadP$14)") (class "Default")
      (node (ref "BLUETOOTH") (pin "P$14") (pinfunction "P$14_PIO(8)_P$14") (pintype "bidirectional"))
    )
    (net (code "234") (name "unconnected-(BLUETOOTH-P$15_PIO(9)-PadP$15)") (class "Default")
      (node (ref "BLUETOOTH") (pin "P$15") (pinfunction "P$15_PIO(9)_P$15") (pintype "bidirectional"))
    )
    (net (code "235") (name "unconnected-(BLUETOOTH-P$16_RESET-PadP$16)") (class "Default")
      (node (ref "BLUETOOTH") (pin "P$16") (pinfunction "P$16_RESET_P$16") (pintype "input"))
    )
    (net (code "236") (name "unconnected-(BLUETOOTH-P$20_USB-DP-PadP$20)") (class "Default")
      (node (ref "BLUETOOTH") (pin "P$20") (pinfunction "P$20_USB-DP_P$20") (pintype "bidirectional"))
    )
    (net (code "237") (name "unconnected-(BLUETOOTH-P$21_USB-DN-PadP$21)") (class "Default")
      (node (ref "BLUETOOTH") (pin "P$21") (pinfunction "P$21_USB-DN_P$21") (pintype "bidirectional"))
    )
    (net (code "238") (name "unconnected-(BLUETOOTH-P$22_PCM-SYNC-PadP$22)") (class "Default")
      (node (ref "BLUETOOTH") (pin "P$22") (pinfunction "P$22_PCM-SYNC_P$22") (pintype "bidirectional"))
    )
    (net (code "239") (name "unconnected-(BLUETOOTH-P$23_PCM-IN-PadP$23)") (class "Default")
      (node (ref "BLUETOOTH") (pin "P$23") (pinfunction "P$23_PCM-IN_P$23") (pintype "input"))
    )
    (net (code "240") (name "unconnected-(BLUETOOTH-P$24_PCM-OUT-PadP$24)") (class "Default")
      (node (ref "BLUETOOTH") (pin "P$24") (pinfunction "P$24_PCM-OUT_P$24") (pintype "output"))
    )
    (net (code "241") (name "unconnected-(BLUETOOTH-P$25_PCM-CLK-PadP$25)") (class "Default")
      (node (ref "BLUETOOTH") (pin "P$25") (pinfunction "P$25_PCM-CLK_P$25") (pintype "bidirectional"))
    )
    (net (code "242") (name "unconnected-(BLUETOOTH-P$28_UART-RTS-PadP$28)") (class "Default")
      (node (ref "BLUETOOTH") (pin "P$28") (pinfunction "P$28_UART-RTS_P$28") (pintype "output"))
    )
    (net (code "243") (name "unconnected-(BLUETOOTH-P$30_UART-CTS-PadP$30)") (class "Default")
      (node (ref "BLUETOOTH") (pin "P$30") (pinfunction "P$30_UART-CTS_P$30") (pintype "input"))
    )
    (net (code "244") (name "unconnected-(BLUETOOTH-P$31_SPI-MOSI-PadP$31)") (class "Default")
      (node (ref "BLUETOOTH") (pin "P$31") (pinfunction "P$31_SPI-MOSI_P$31") (pintype "input"))
    )
    (net (code "245") (name "unconnected-(BLUETOOTH-P$32_SPI-CSB-PadP$32)") (class "Default")
      (node (ref "BLUETOOTH") (pin "P$32") (pinfunction "P$32_SPI-CSB_P$32") (pintype "input"))
    )
    (net (code "246") (name "unconnected-(BLUETOOTH-P$33_SPI-CLK-PadP$33)") (class "Default")
      (node (ref "BLUETOOTH") (pin "P$33") (pinfunction "P$33_SPI-CLK_P$33") (pintype "input"))
    )
    (net (code "247") (name "unconnected-(BLUETOOTH-P$34_SPI-MISO-PadP$34)") (class "Default")
      (node (ref "BLUETOOTH") (pin "P$34") (pinfunction "P$34_SPI-MISO_P$34") (pintype "output"))
    )
    (net (code "248") (name "unconnected-(BLUETOOTH-P$35_PIO(11)-PadP$35)") (class "Default")
      (node (ref "BLUETOOTH") (pin "P$35") (pinfunction "P$35_PIO(11)_P$35") (pintype "bidirectional"))
    )
    (net (code "249") (name "unconnected-(BLUETOOTH-P$36_PIO(10)-PadP$36)") (class "Default")
      (node (ref "BLUETOOTH") (pin "P$36") (pinfunction "P$36_PIO(10)_P$36") (pintype "bidirectional"))
    )
    (net (code "250") (name "unconnected-(GPS-DMINUS-PadD+)") (class "Default")
      (node (ref "GPS") (pin "D+") (pinfunction "DMINUS_D+") (pintype "bidirectional"))
    )
    (net (code "251") (name "unconnected-(GPS-DPLUS-PadD-)") (class "Default")
      (node (ref "GPS") (pin "D-") (pinfunction "DPLUS_D-") (pintype "bidirectional"))
    )
    (net (code "252") (name "unconnected-(IC4-(T1)PD6-Pad49)") (class "Default")
      (node (ref "IC4") (pin "49") (pinfunction "(T1)PD6_49") (pintype "bidirectional"))
    )
    (net (code "253") (name "unconnected-(IC4-(TOSC1)PG4-Pad29)") (class "Default")
      (node (ref "IC4") (pin "29") (pinfunction "(TOSC1)PG4_29") (pintype "bidirectional"))
    )
    (net (code "254") (name "unconnected-(IC4-(TOSC2)PG3-Pad28)") (class "Default")
      (node (ref "IC4") (pin "28") (pinfunction "(TOSC2)PG3_28") (pintype "bidirectional"))
    )
    (net (code "255") (name "unconnected-(IC4-(XCK0{slash}AIN0)PE2-Pad4)") (class "Default")
      (node (ref "IC4") (pin "4") (pinfunction "(XCK0/AIN0)PE2_4") (pintype "bidirectional"))
    )
    (net (code "256") (name "unconnected-(IC4-(XCK1)PD5-Pad48)") (class "Default")
      (node (ref "IC4") (pin "48") (pinfunction "(XCK1)PD5_48") (pintype "bidirectional"))
    )
    (net (code "257") (name "unconnected-(IC4-PH0(RXD2)-Pad12)") (class "Default")
      (node (ref "IC4") (pin "12") (pinfunction "PH0(RXD2)_12") (pintype "bidirectional"))
    )
    (net (code "258") (name "unconnected-(IC4-PH1(TXD2)-Pad13)") (class "Default")
      (node (ref "IC4") (pin "13") (pinfunction "PH1(TXD2)_13") (pintype "bidirectional"))
    )
    (net (code "259") (name "unconnected-(IC4-PH2(XCK2)-Pad14)") (class "Default")
      (node (ref "IC4") (pin "14") (pinfunction "PH2(XCK2)_14") (pintype "bidirectional"))
    )
    (net (code "260") (name "unconnected-(IC4-PH7(T4)-Pad27)") (class "Default")
      (node (ref "IC4") (pin "27") (pinfunction "PH7(T4)_27") (pintype "bidirectional"))
    )
    (net (code "261") (name "unconnected-(IC4-PJ2(XCK3{slash}PCINT11)-Pad65)") (class "Default")
      (node (ref "IC4") (pin "65") (pinfunction "PJ2(XCK3/PCINT11)_65") (pintype "bidirectional"))
    )
    (net (code "262") (name "unconnected-(IC4-PJ7-Pad79)") (class "Default")
      (node (ref "IC4") (pin "79") (pinfunction "PJ7_79") (pintype "bidirectional"))
    )
    (net (code "263") (name "unconnected-(NHD_2.7-NC-PadNC0)") (class "Default")
      (node (ref "NHD_2.7") (pin "NC0") (pinfunction "NC_NC0") (pintype "bidirectional"))
    )
    (net (code "264") (name "unconnected-(NHD_2.7-NC2-PadNC1)") (class "Default")
      (node (ref "NHD_2.7") (pin "NC1") (pinfunction "NC2_NC1") (pintype "bidirectional"))
    )
    (net (code "265") (name "unconnected-(NHD_2.7-NC3-PadNC2)") (class "Default")
      (node (ref "NHD_2.7") (pin "NC2") (pinfunction "NC3_NC2") (pintype "bidirectional"))
    )
    (net (code "266") (name "unconnected-(NHD_2.7-NC4-PadNC3)") (class "Default")
      (node (ref "NHD_2.7") (pin "NC3") (pinfunction "NC4_NC3") (pintype "bidirectional"))
    )
    (net (code "267") (name "unconnected-(R_E2_0-Pad1)") (class "Default")
      (node (ref "R_E2_0") (pin "1") (pinfunction "1_1") (pintype "passive"))
    )
    (net (code "268") (name "unconnected-(ST2-DAT1-Pad8)") (class "Default")
      (node (ref "ST2") (pin "8") (pinfunction "DAT1_8") (pintype "bidirectional"))
    )
    (net (code "269") (name "unconnected-(ST2-DAT2-Pad1)") (class "Default")
      (node (ref "ST2") (pin "1") (pinfunction "DAT2_1") (pintype "bidirectional"))
    )
    (net (code "270") (name "unconnected-(U$1-(ADC4{slash}PCINT12{slash}SDA)PC4-Pad27)") (class "Default")
      (node (ref "U$1") (pin "27") (pinfunction "(ADC4/PCINT12/SDA)PC4_27") (pintype "output"))
    )
    (net (code "271") (name "unconnected-(U$1-(PCINT0{slash}CLKO{slash}ICP1)PB0-Pad12)") (class "Default")
      (node (ref "U$1") (pin "12") (pinfunction "(PCINT0/CLKO/ICP1)PB0_12") (pintype "bidirectional"))
    )
    (net (code "272") (name "unconnected-(U$1-(PCINT1{slash}OC1A)PB1-Pad13)") (class "Default")
      (node (ref "U$1") (pin "13") (pinfunction "(PCINT1/OC1A)PB1_13") (pintype "bidirectional"))
    )
    (net (code "273") (name "unconnected-(U$1-(PCINT2{slash}~{SS}{slash}OC1B)PB2-Pad14)") (class "Default")
      (node (ref "U$1") (pin "14") (pinfunction "(PCINT2/~{SS}/OC1B)PB2_14") (pintype "bidirectional"))
    )
    (net (code "274") (name "unconnected-(U$1-ADC6-Pad19)") (class "Default")
      (node (ref "U$1") (pin "19") (pinfunction "ADC6_19") (pintype "bidirectional"))
    )
    (net (code "275") (name "unconnected-(U$1-ADC7-Pad22)") (class "Default")
      (node (ref "U$1") (pin "22") (pinfunction "ADC7_22") (pintype "bidirectional"))
    )
    (net (code "276") (name "unconnected-(U$14-A0-Pad2)") (class "Default")
      (node (ref "U$14") (pin "2") (pinfunction "A0_2") (pintype "bidirectional"))
    )
    (net (code "277") (name "unconnected-(U$14-A1-Pad3)") (class "Default")
      (node (ref "U$14") (pin "3") (pinfunction "A1_3") (pintype "bidirectional"))
    )
    (net (code "278") (name "unconnected-(U$14-A2-Pad4)") (class "Default")
      (node (ref "U$14") (pin "4") (pinfunction "A2_4") (pintype "bidirectional"))
    )
    (net (code "279") (name "unconnected-(U$14-A3-Pad5)") (class "Default")
      (node (ref "U$14") (pin "5") (pinfunction "A3_5") (pintype "bidirectional"))
    )
    (net (code "280") (name "unconnected-(U$14-A4-Pad6)") (class "Default")
      (node (ref "U$14") (pin "6") (pinfunction "A4_6") (pintype "bidirectional"))
    )
    (net (code "281") (name "unconnected-(U$14-B0-Pad18)") (class "Default")
      (node (ref "U$14") (pin "18") (pinfunction "B0_18") (pintype "bidirectional"))
    )
    (net (code "282") (name "unconnected-(U$14-B1-Pad17)") (class "Default")
      (node (ref "U$14") (pin "17") (pinfunction "B1_17") (pintype "bidirectional"))
    )
    (net (code "283") (name "unconnected-(U$14-B2-Pad16)") (class "Default")
      (node (ref "U$14") (pin "16") (pinfunction "B2_16") (pintype "bidirectional"))
    )
    (net (code "284") (name "unconnected-(U$14-B3-Pad15)") (class "Default")
      (node (ref "U$14") (pin "15") (pinfunction "B3_15") (pintype "bidirectional"))
    )
    (net (code "285") (name "unconnected-(U$14-B4-Pad14)") (class "Default")
      (node (ref "U$14") (pin "14") (pinfunction "B4_14") (pintype "bidirectional"))
    )
    (net (code "286") (name "unconnected-(U$19-INTA-Pad20)") (class "Default")
      (node (ref "U$19") (pin "20") (pinfunction "INTA_20") (pintype "bidirectional"))
    )
    (net (code "287") (name "unconnected-(U$19-INTB-Pad19)") (class "Default")
      (node (ref "U$19") (pin "19") (pinfunction "INTB_19") (pintype "bidirectional"))
    )
    (net (code "288") (name "unconnected-(U$19-NC1-Pad11)") (class "Default")
      (node (ref "U$19") (pin "11") (pinfunction "NC1_11") (pintype "bidirectional"))
    )
    (net (code "289") (name "unconnected-(U$19-NC2-Pad14)") (class "Default")
      (node (ref "U$19") (pin "14") (pinfunction "NC2_14") (pintype "bidirectional"))
    )
  )
)
